# Audio_Spektrum_Analysator.net
KiCad netlist of a schematic drawn in EAGLE
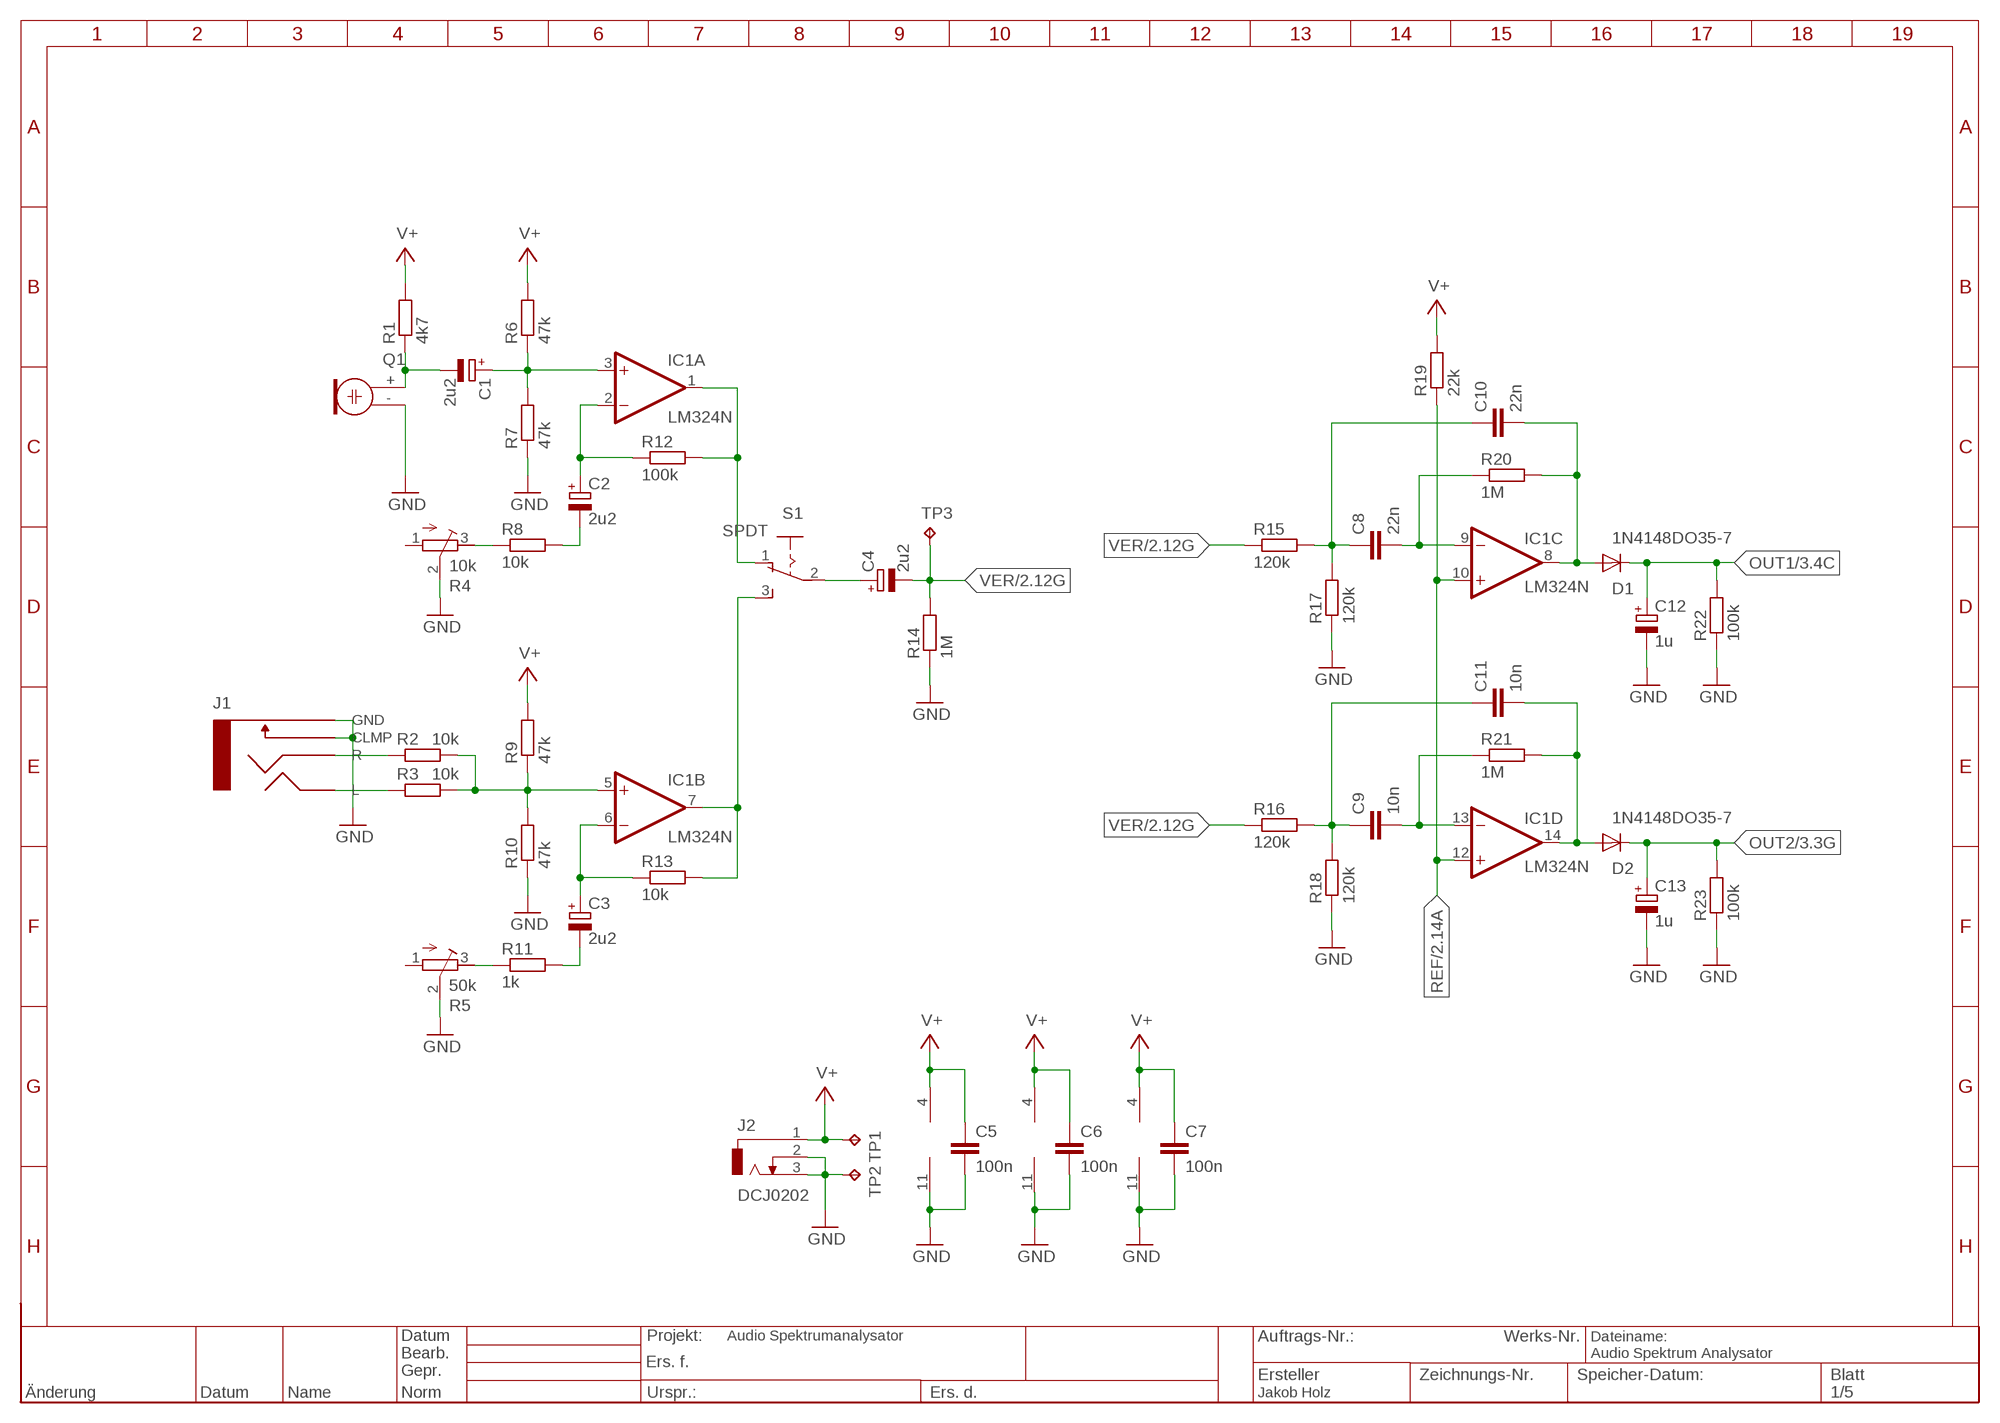
[diagram p0: schematic, sheet 1]
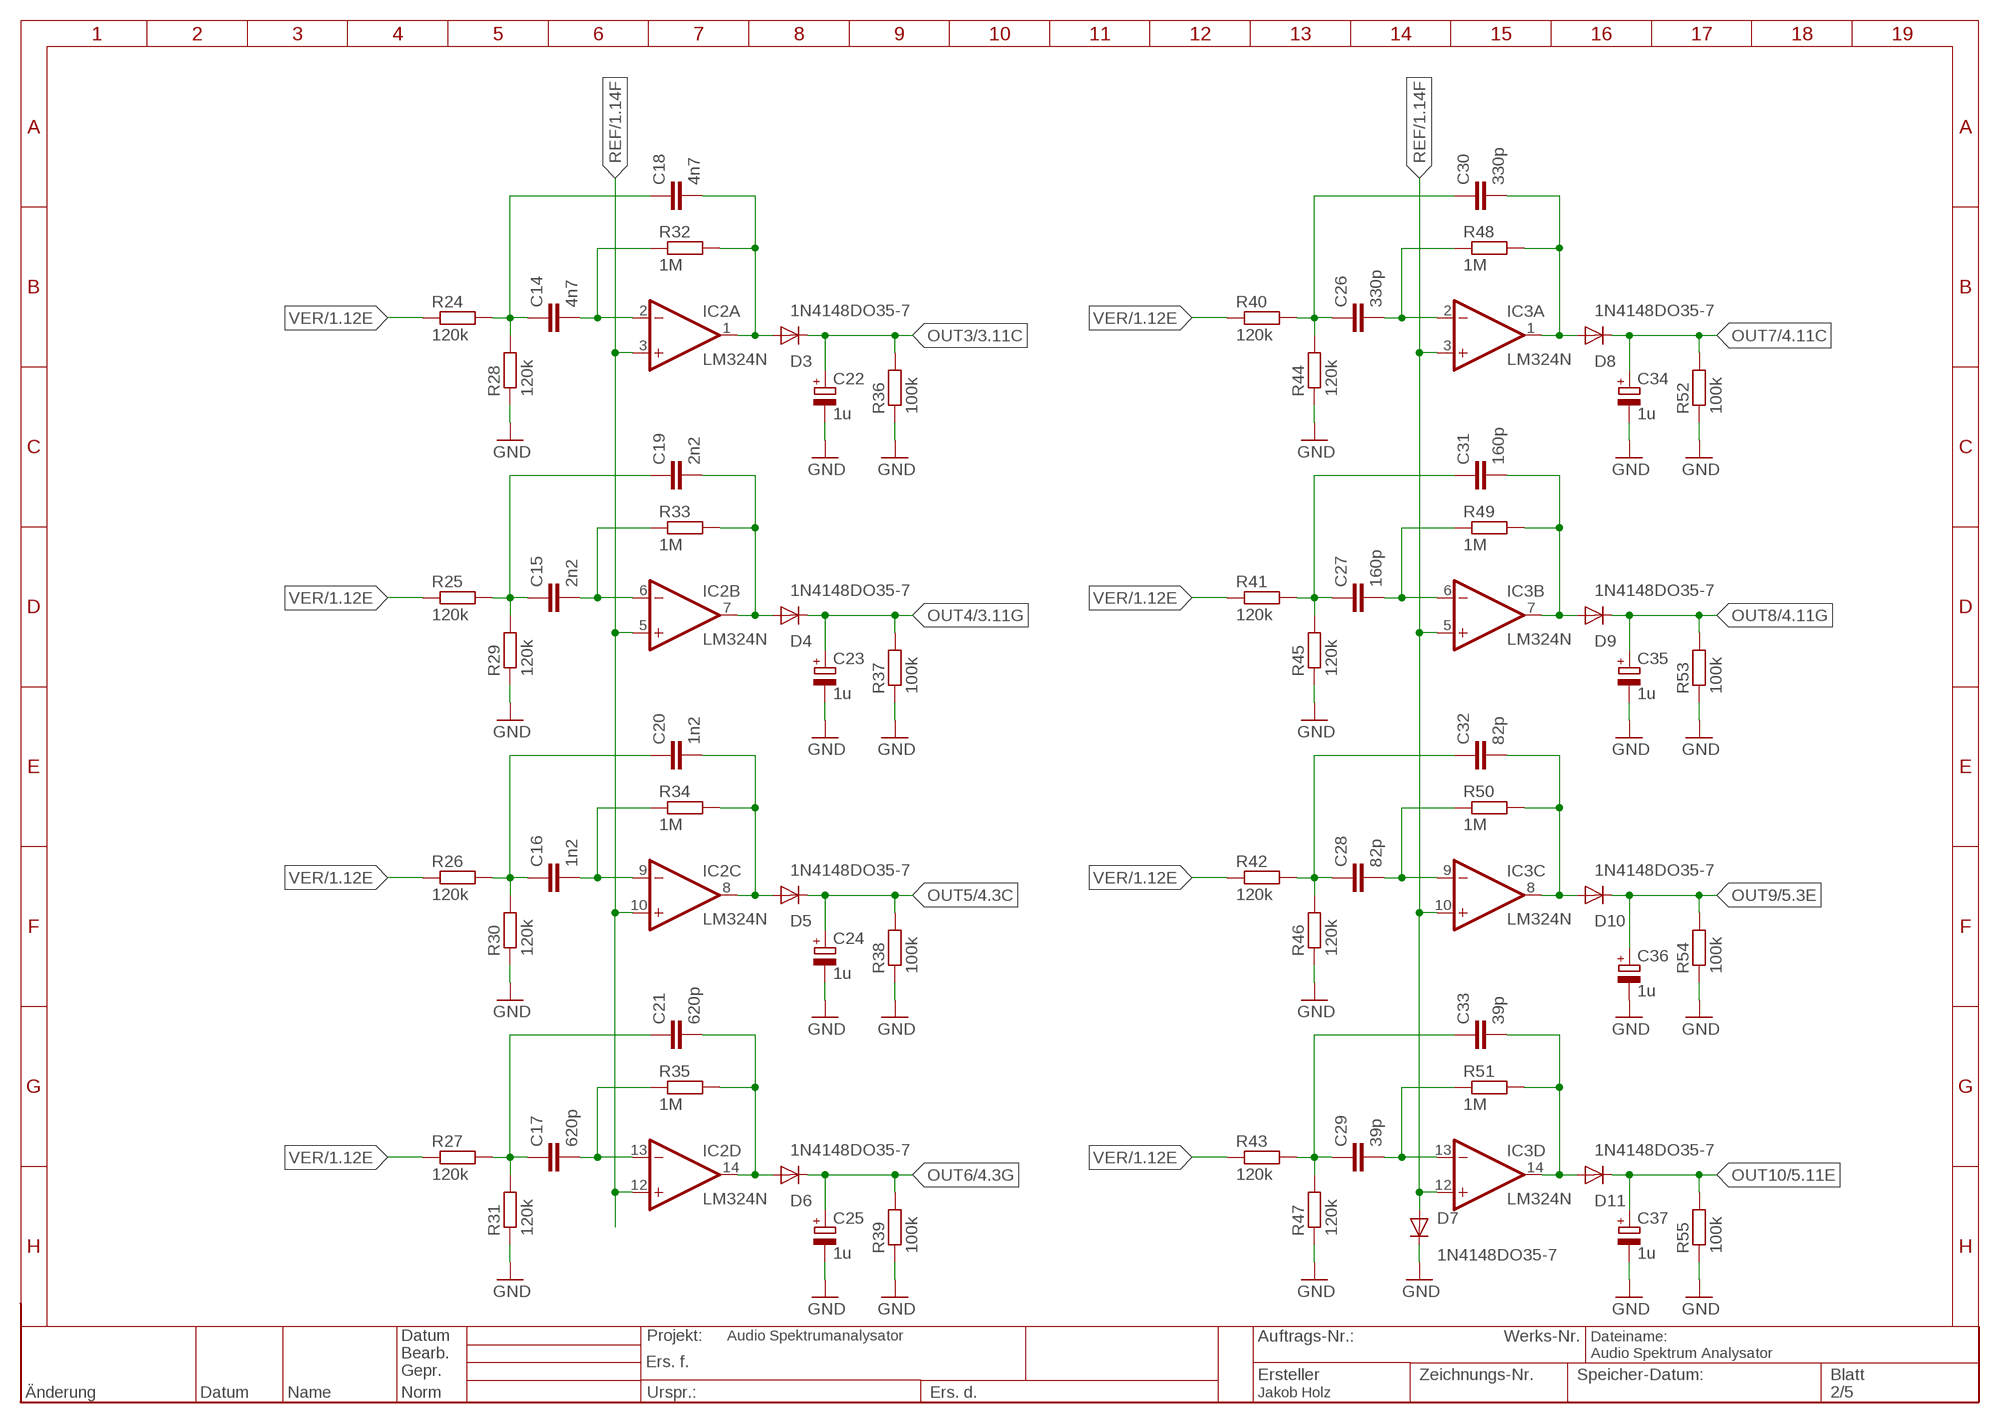
[diagram p1: schematic, sheet 2]
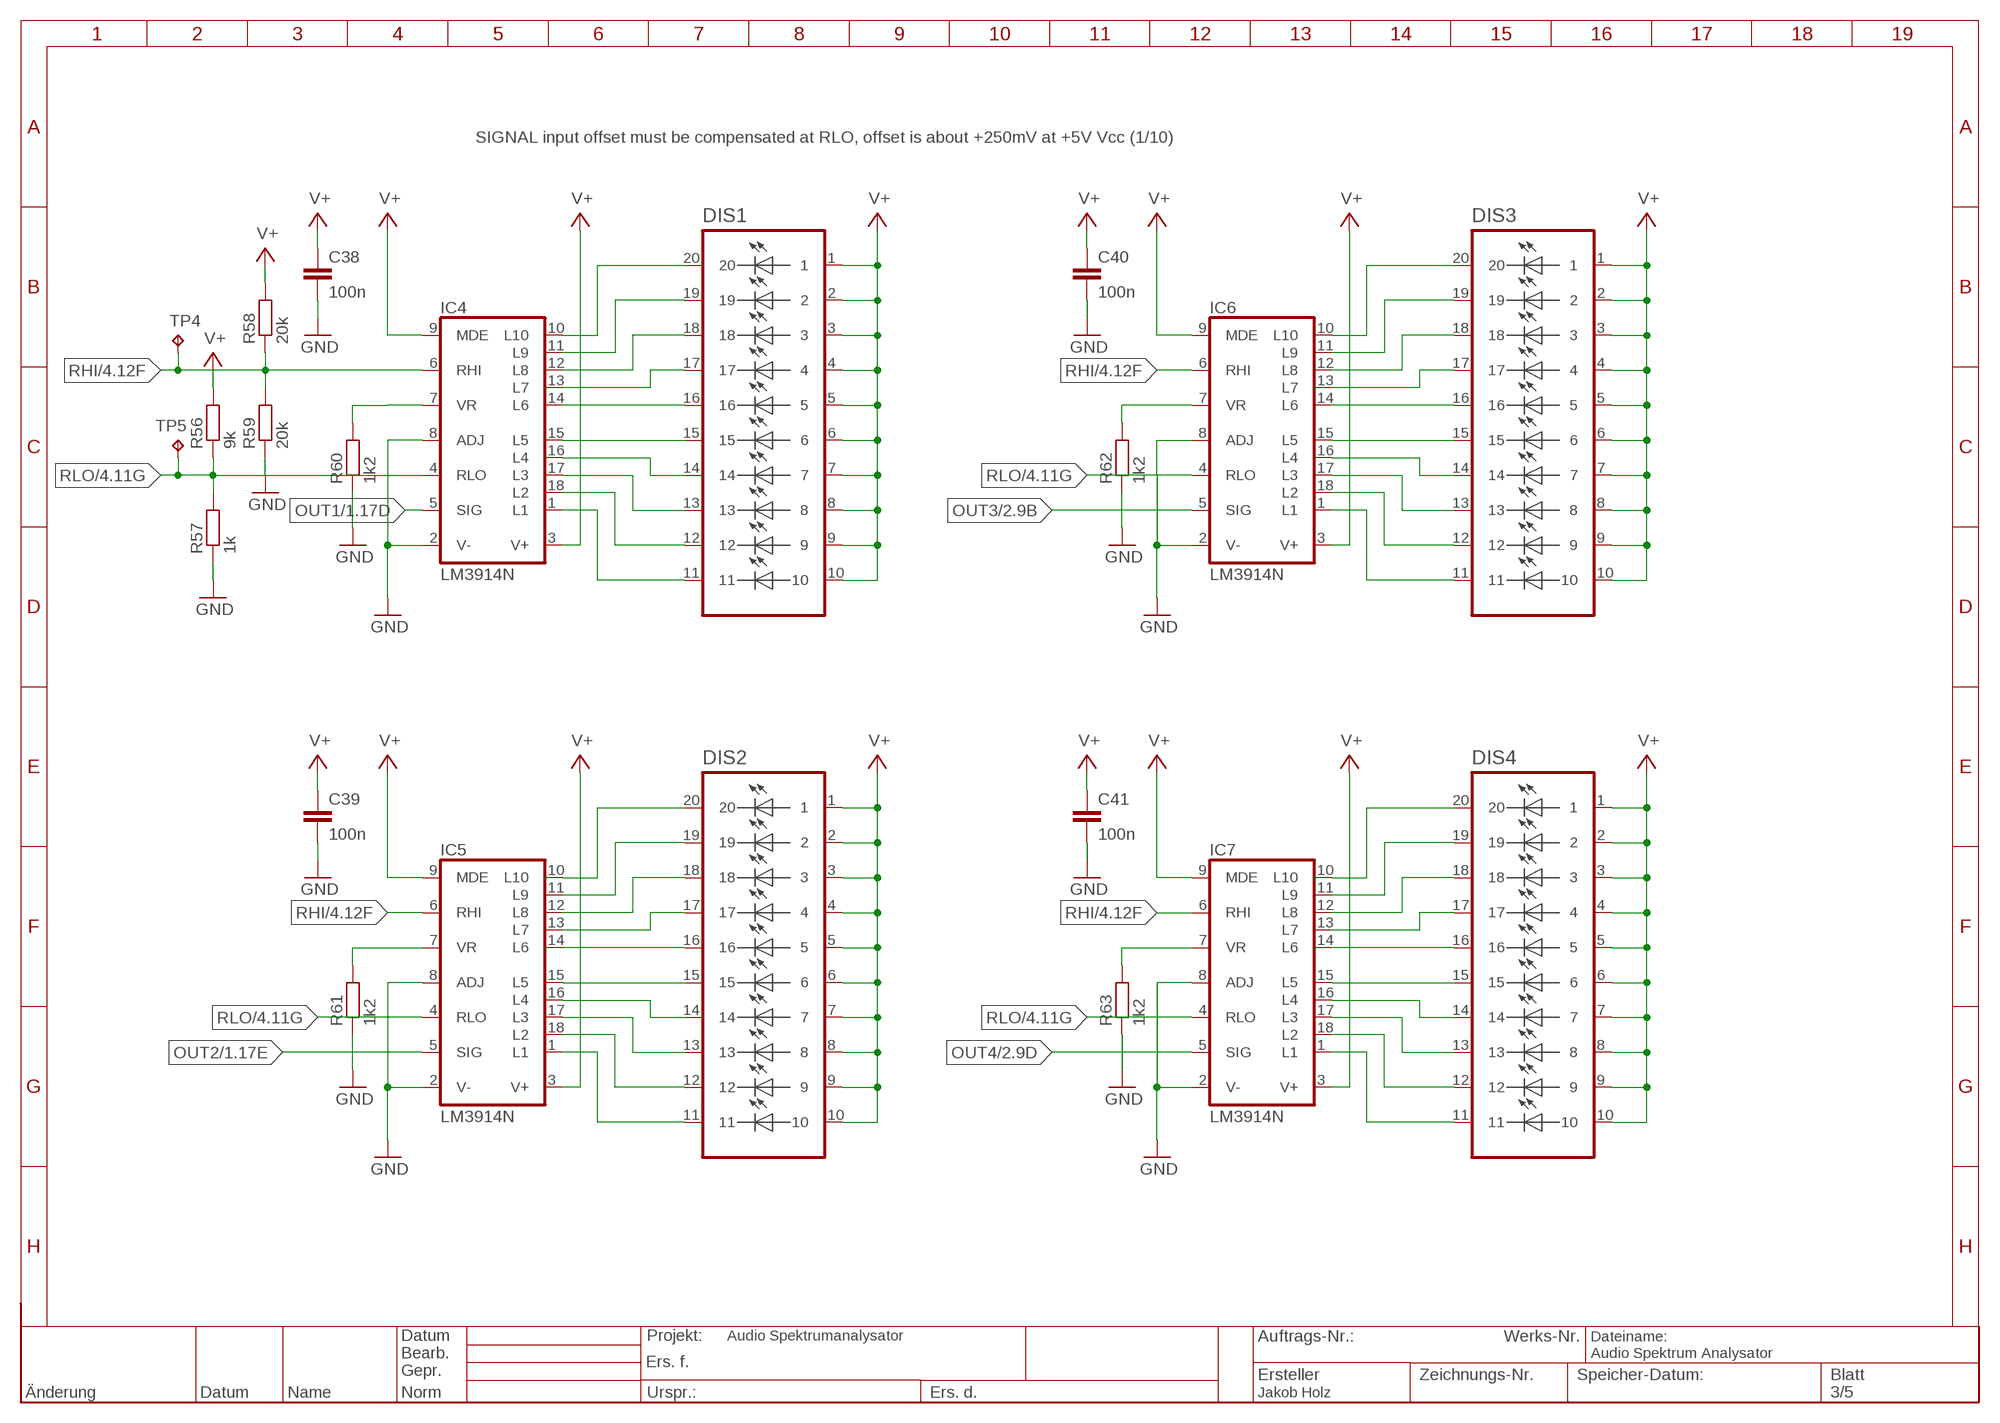
[diagram p2: schematic, sheet 3]
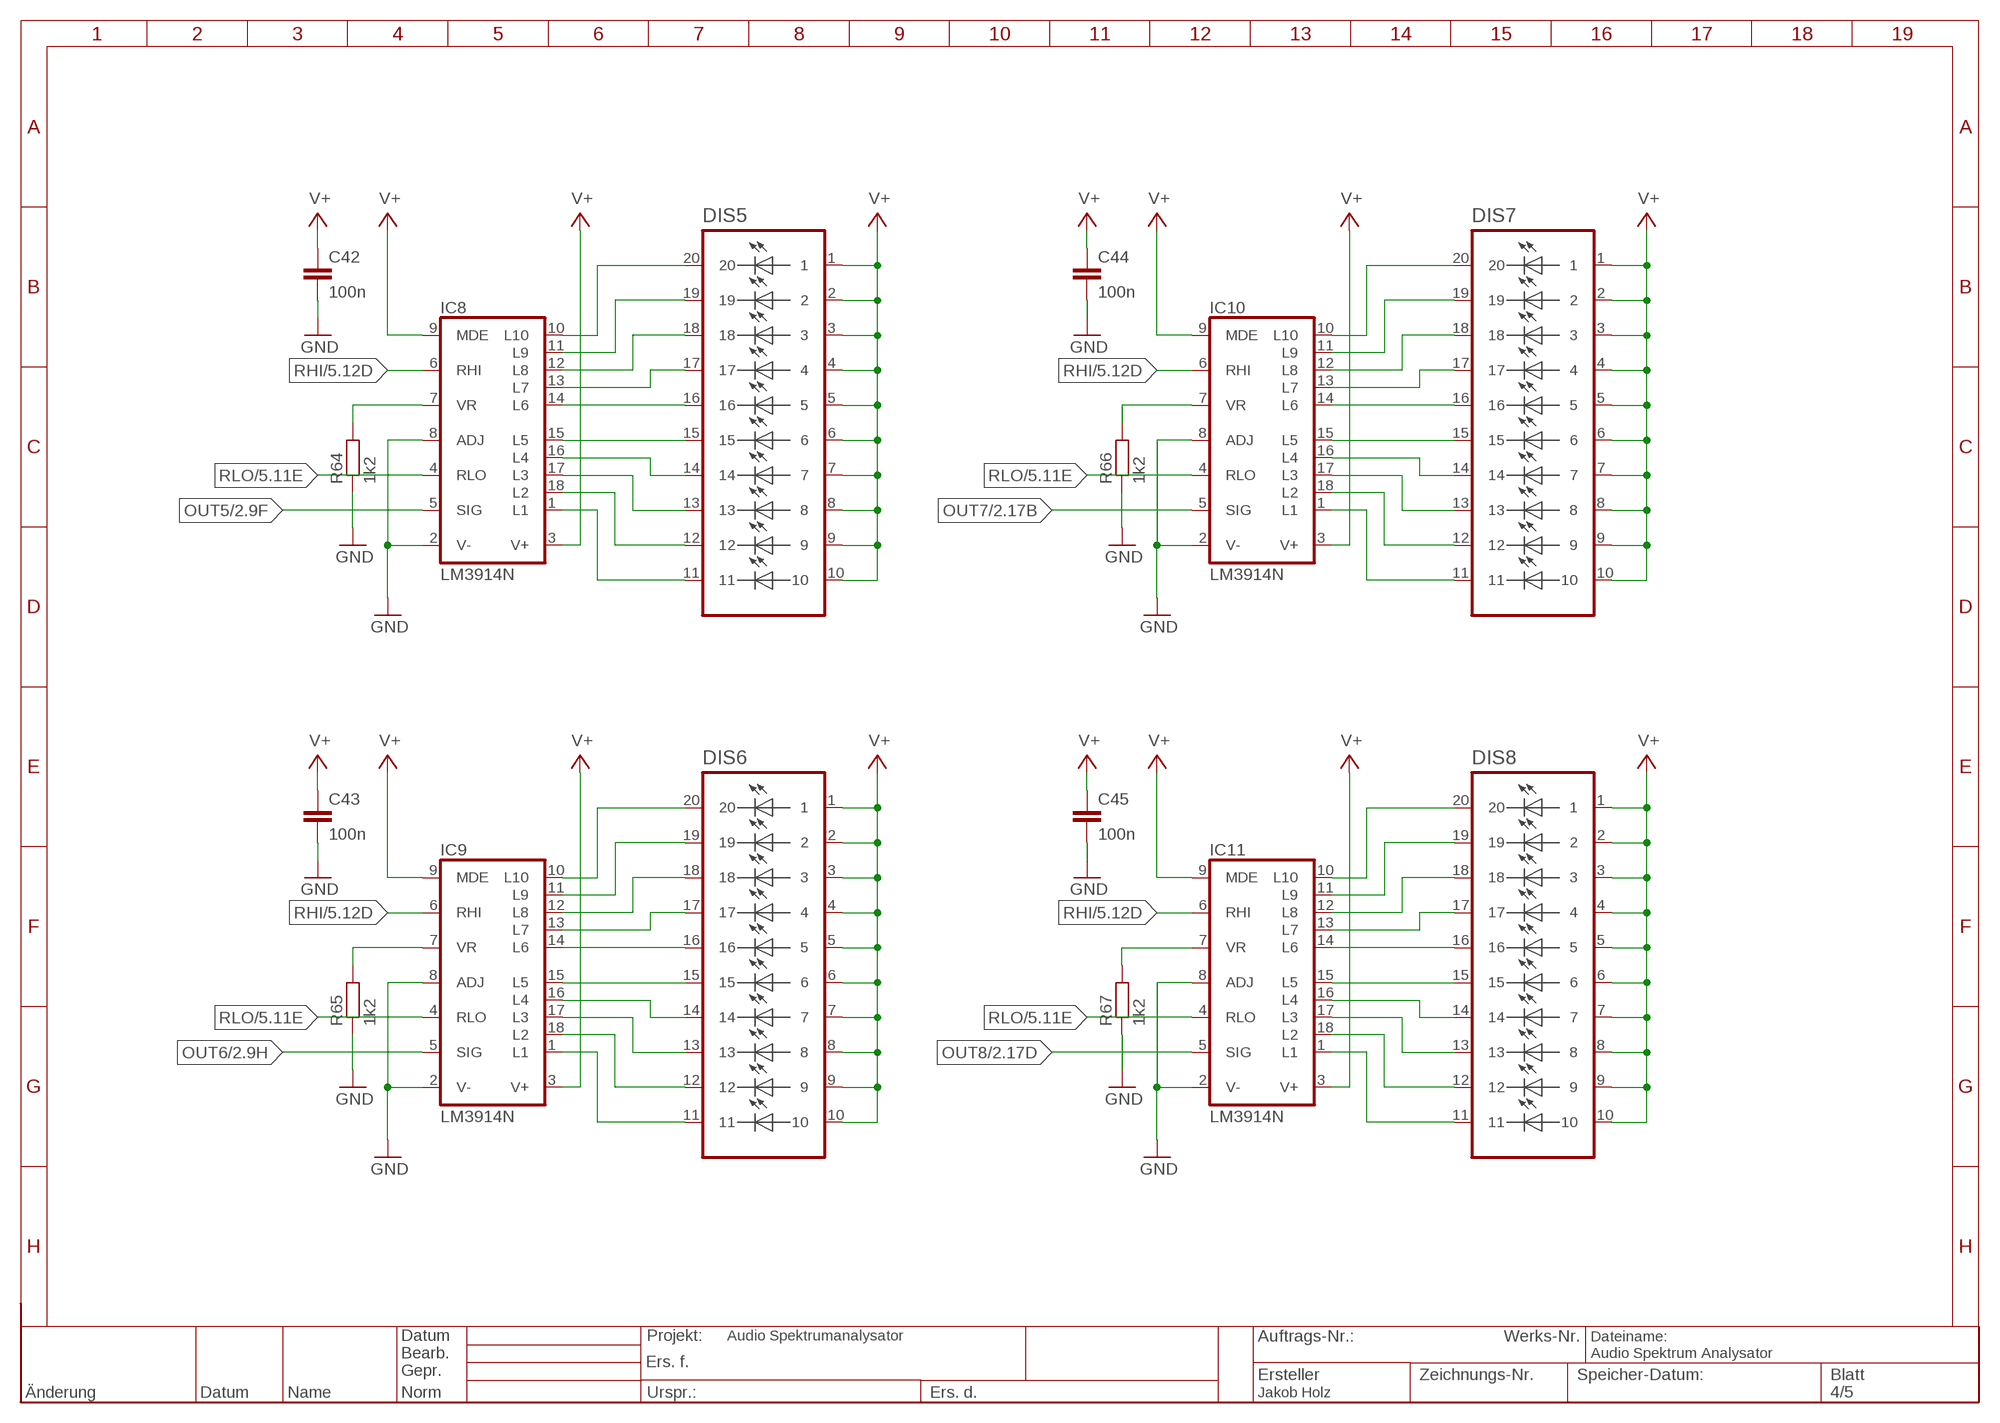
[diagram p3: schematic, sheet 4]
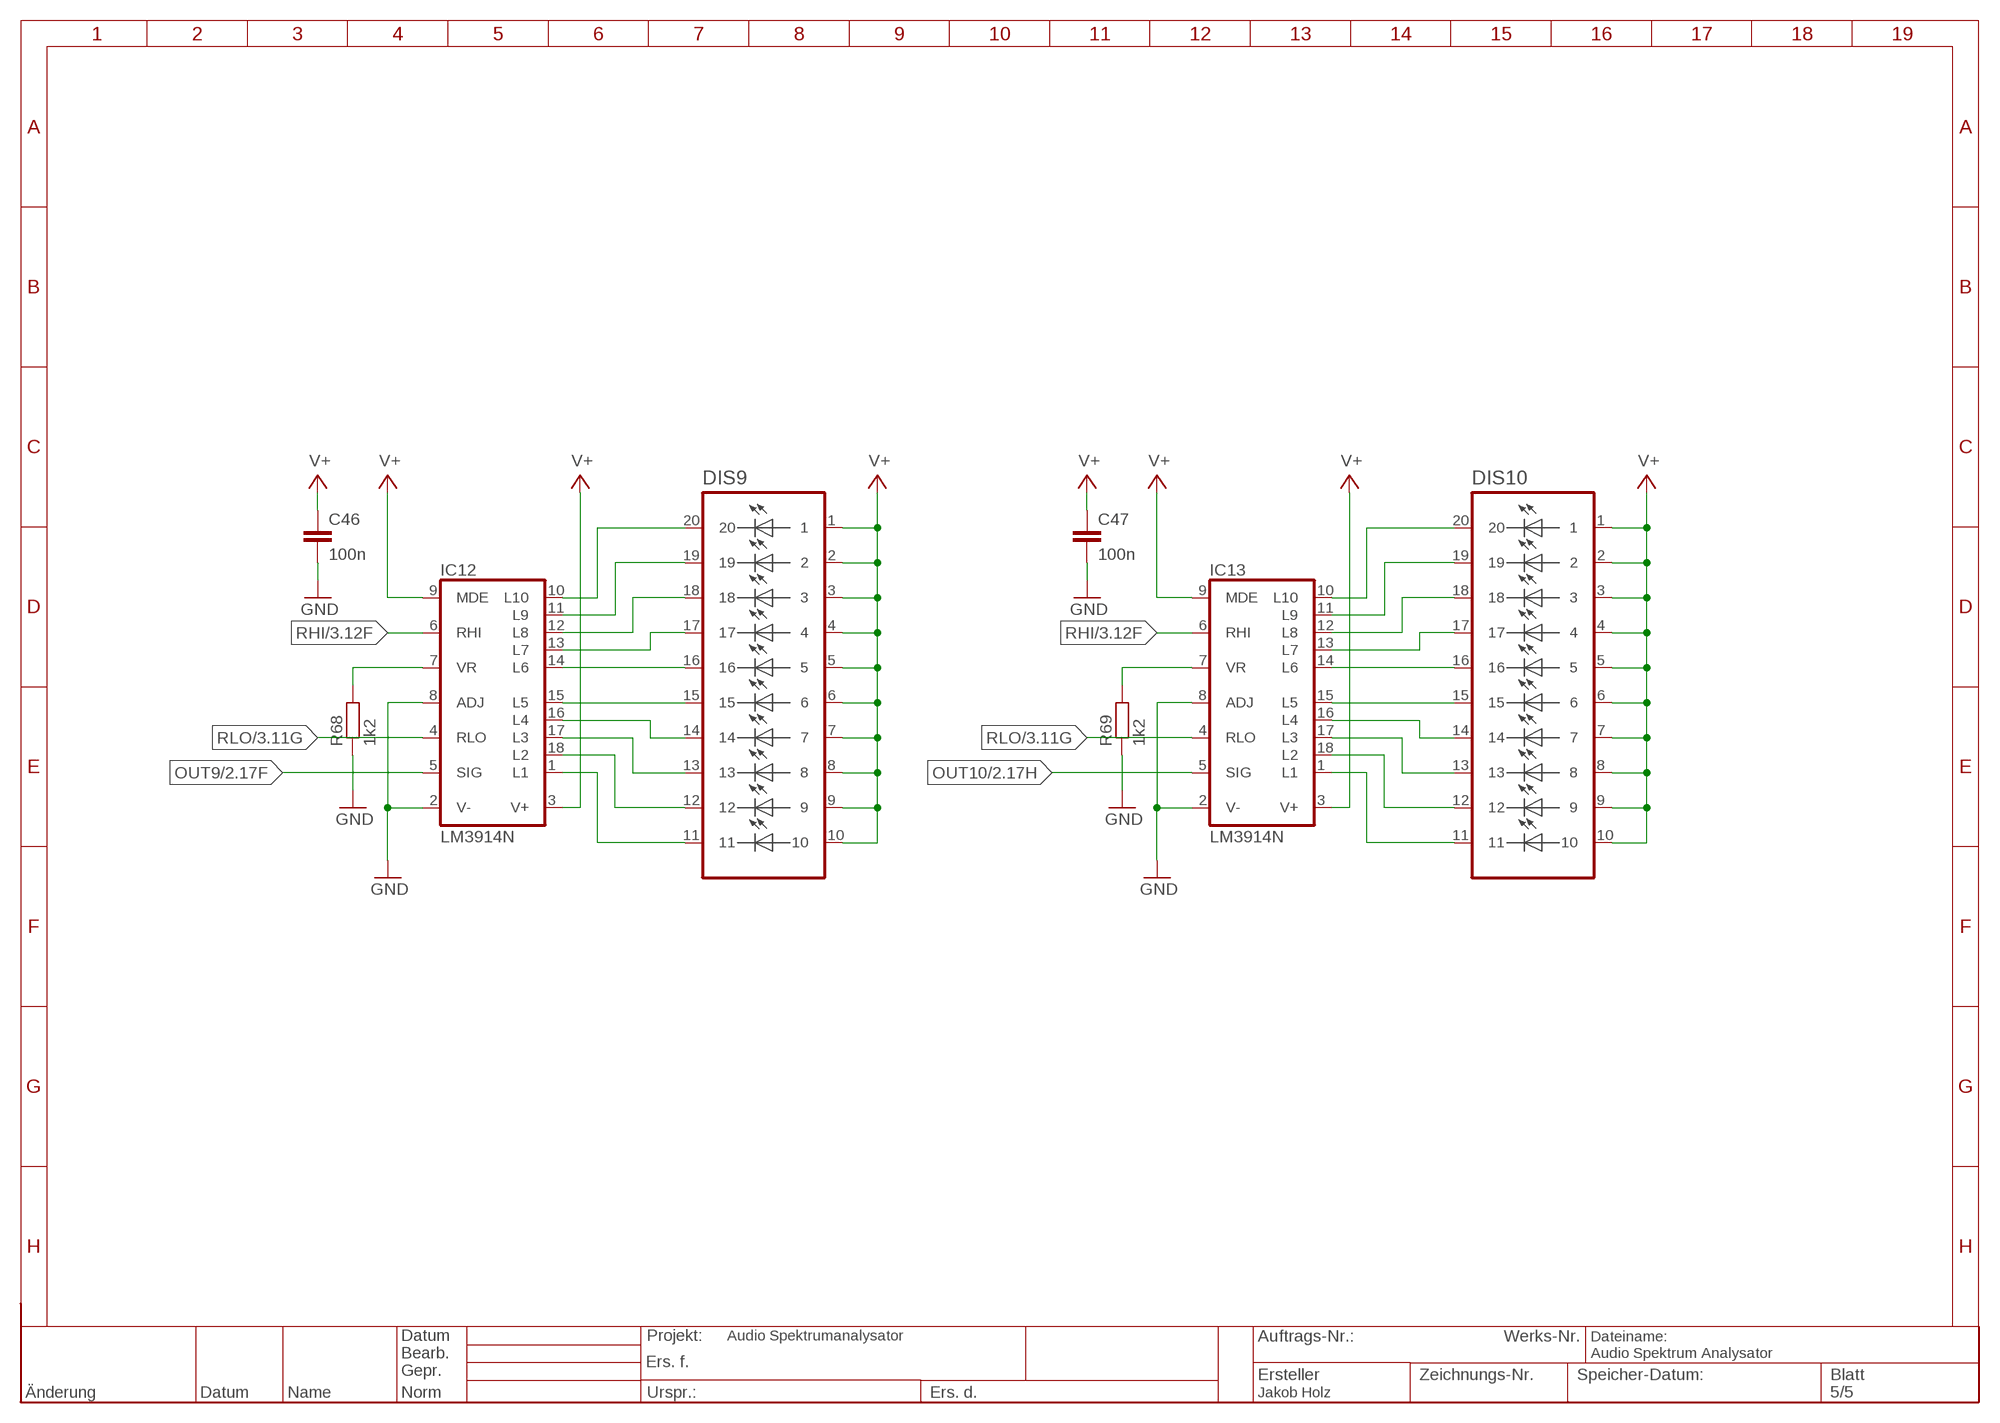
[diagram p4: schematic, sheet 5]

(export (version "E")
  (design (tool "Eeschema 10.0.6"))
  (components
    (comp (ref "C42")
      (value "100n")
      (footprint "eagle-import:C050-024X044")
      (libsource (lib "eagle-import") (part "C-EU050-024X044"))
    )
    (comp (ref "C43")
      (value "100n")
      (footprint "eagle-import:C050-024X044")
      (libsource (lib "eagle-import") (part "C-EU050-024X044"))
    )
    (comp (ref "C44")
      (value "100n")
      (footprint "eagle-import:C050-024X044")
      (libsource (lib "eagle-import") (part "C-EU050-024X044"))
    )
    (comp (ref "C45")
      (value "100n")
      (footprint "eagle-import:C050-024X044")
      (libsource (lib "eagle-import") (part "C-EU050-024X044"))
    )
    (comp (ref "DIS5")
      (value "SHB10R")
      (footprint "eagle-import:SHB10R")
      (libsource (lib "eagle-import") (part "SHB10R"))
    )
    (comp (ref "DIS6")
      (value "SHB10R")
      (footprint "eagle-import:SHB10R")
      (libsource (lib "eagle-import") (part "SHB10R"))
    )
    (comp (ref "DIS7")
      (value "SHB10R")
      (footprint "eagle-import:SHB10R")
      (libsource (lib "eagle-import") (part "SHB10R"))
    )
    (comp (ref "DIS8")
      (value "SHB10R")
      (footprint "eagle-import:SHB10R")
      (libsource (lib "eagle-import") (part "SHB10R"))
    )
    (comp (ref "IC8")
      (value "LM3914N")
      (footprint "eagle-import:DIL18")
      (libsource (lib "eagle-import") (part "LM3914N"))
    )
    (comp (ref "IC9")
      (value "LM3914N")
      (footprint "eagle-import:DIL18")
      (libsource (lib "eagle-import") (part "LM3914N"))
    )
    (comp (ref "IC10")
      (value "LM3914N")
      (footprint "eagle-import:DIL18")
      (libsource (lib "eagle-import") (part "LM3914N"))
    )
    (comp (ref "IC11")
      (value "LM3914N")
      (footprint "eagle-import:DIL18")
      (libsource (lib "eagle-import") (part "LM3914N"))
    )
    (comp (ref "R64")
      (value "1k2")
      (footprint "eagle-import:0207_7")
      (libsource (lib "eagle-import") (part "resistor_348_R-EU_0207/7"))
    )
    (comp (ref "R65")
      (value "1k2")
      (footprint "eagle-import:0207_7")
      (libsource (lib "eagle-import") (part "resistor_348_R-EU_0207/7"))
    )
    (comp (ref "R66")
      (value "1k2")
      (footprint "eagle-import:0207_7")
      (libsource (lib "eagle-import") (part "resistor_348_R-EU_0207/7"))
    )
    (comp (ref "R67")
      (value "1k2")
      (footprint "eagle-import:0207_7")
      (libsource (lib "eagle-import") (part "resistor_348_R-EU_0207/7"))
    )
    (comp (ref "C1")
      (value "2u2")
      (footprint "eagle-import:E2,5-5")
      (libsource (lib "eagle-import") (part "CPOL-EUE2.5-5"))
    )
    (comp (ref "C2")
      (value "2u2")
      (footprint "eagle-import:E2,5-5")
      (libsource (lib "eagle-import") (part "CPOL-EUE2.5-5"))
    )
    (comp (ref "C3")
      (value "2u2")
      (footprint "eagle-import:E2,5-5")
      (libsource (lib "eagle-import") (part "CPOL-EUE2.5-5"))
    )
    (comp (ref "C4")
      (value "2u2")
      (footprint "eagle-import:E2,5-5")
      (libsource (lib "eagle-import") (part "CPOL-EUE2.5-5"))
    )
    (comp (ref "C5")
      (value "100n")
      (footprint "eagle-import:C050-024X044")
      (libsource (lib "eagle-import") (part "C-EU050-024X044"))
    )
    (comp (ref "C6")
      (value "100n")
      (footprint "eagle-import:C050-024X044")
      (libsource (lib "eagle-import") (part "C-EU050-024X044"))
    )
    (comp (ref "C7")
      (value "100n")
      (footprint "eagle-import:C050-024X044")
      (libsource (lib "eagle-import") (part "C-EU050-024X044"))
    )
    (comp (ref "C8")
      (value "22n")
      (footprint "eagle-import:C025-024X044")
      (libsource (lib "eagle-import") (part "C-EU025-024X044"))
    )
    (comp (ref "C9")
      (value "10n")
      (footprint "eagle-import:C025-024X044")
      (libsource (lib "eagle-import") (part "C-EU025-024X044"))
    )
    (comp (ref "C10")
      (value "22n")
      (footprint "eagle-import:C025-024X044")
      (libsource (lib "eagle-import") (part "C-EU025-024X044"))
    )
    (comp (ref "C11")
      (value "10n")
      (footprint "eagle-import:C025-024X044")
      (libsource (lib "eagle-import") (part "C-EU025-024X044"))
    )
    (comp (ref "C12")
      (value "1u")
      (footprint "eagle-import:E2,5-5")
      (libsource (lib "eagle-import") (part "CPOL-EUE2.5-5"))
    )
    (comp (ref "C13")
      (value "1u")
      (footprint "eagle-import:E2,5-5")
      (libsource (lib "eagle-import") (part "CPOL-EUE2.5-5"))
    )
    (comp (ref "D1")
      (value "1N4148DO35-7")
      (footprint "eagle-import:DO35-7")
      (libsource (lib "eagle-import") (part "1N4148DO35-7"))
    )
    (comp (ref "D2")
      (value "1N4148DO35-7")
      (footprint "eagle-import:DO35-7")
      (libsource (lib "eagle-import") (part "1N4148DO35-7"))
    )
    (comp (ref "IC1")
      (value "LM324N")
      (footprint "eagle-import:DIL14")
      (libsource (lib "eagle-import") (part "LM324N"))
    )
    (comp (ref "IC2")
      (value "LM324N")
      (footprint "eagle-import:DIL14")
      (libsource (lib "eagle-import") (part "LM324N"))
    )
    (comp (ref "IC3")
      (value "LM324N")
      (footprint "eagle-import:DIL14")
      (libsource (lib "eagle-import") (part "LM324N"))
    )
    (comp (ref "J1")
      (value "2.5MM-AUXS")
      (footprint "eagle-import:2,5MM-AUX_JACK")
      (libsource (lib "eagle-import") (part "2.5MM-AUXS"))
    )
    (comp (ref "J2")
      (value "DCJ0202")
      (footprint "eagle-import:DCJ0202")
      (libsource (lib "eagle-import") (part "DCJ0202"))
    )
    (comp (ref "Q1")
      (value "ELECTRET")
      (footprint "eagle-import:9.7ELECTRET")
      (libsource (lib "eagle-import") (part "ELECTRET"))
    )
    (comp (ref "R1")
      (value "4k7")
      (footprint "eagle-import:0207_7")
      (libsource (lib "eagle-import") (part "R-EU_0207/7"))
    )
    (comp (ref "R2")
      (value "10k")
      (footprint "eagle-import:0207_7")
      (libsource (lib "eagle-import") (part "R-EU_0207/7"))
    )
    (comp (ref "R3")
      (value "10k")
      (footprint "eagle-import:0207_7")
      (libsource (lib "eagle-import") (part "R-EU_0207/7"))
    )
    (comp (ref "R4")
      (value "10k")
      (footprint "eagle-import:RTRIM64W")
      (libsource (lib "eagle-import") (part "R-TRIMM64W"))
    )
    (comp (ref "R5")
      (value "50k")
      (footprint "eagle-import:RTRIM64W")
      (libsource (lib "eagle-import") (part "R-TRIMM64W"))
    )
    (comp (ref "R6")
      (value "47k")
      (footprint "eagle-import:0207_7")
      (libsource (lib "eagle-import") (part "R-EU_0207/7"))
    )
    (comp (ref "R7")
      (value "47k")
      (footprint "eagle-import:0207_7")
      (libsource (lib "eagle-import") (part "R-EU_0207/7"))
    )
    (comp (ref "R8")
      (value "10k")
      (footprint "eagle-import:0207_7")
      (libsource (lib "eagle-import") (part "R-EU_0207/7"))
    )
    (comp (ref "R9")
      (value "47k")
      (footprint "eagle-import:0207_7")
      (libsource (lib "eagle-import") (part "R-EU_0207/7"))
    )
    (comp (ref "R10")
      (value "47k")
      (footprint "eagle-import:0207_7")
      (libsource (lib "eagle-import") (part "R-EU_0207/7"))
    )
    (comp (ref "R11")
      (value "1k")
      (footprint "eagle-import:0207_7")
      (libsource (lib "eagle-import") (part "R-EU_0207/7"))
    )
    (comp (ref "R12")
      (value "100k")
      (footprint "eagle-import:0207_7")
      (libsource (lib "eagle-import") (part "R-EU_0207/7"))
    )
    (comp (ref "R13")
      (value "10k")
      (footprint "eagle-import:0207_7")
      (libsource (lib "eagle-import") (part "resistor_348_R-EU_0207/7"))
    )
    (comp (ref "R14")
      (value "1M")
      (footprint "eagle-import:0207_7")
      (libsource (lib "eagle-import") (part "R-EU_0207/7"))
    )
    (comp (ref "R15")
      (value "120k")
      (footprint "eagle-import:0207_7")
      (libsource (lib "eagle-import") (part "resistor_348_R-EU_0207/7"))
    )
    (comp (ref "R16")
      (value "120k")
      (footprint "eagle-import:0207_7")
      (libsource (lib "eagle-import") (part "resistor_348_R-EU_0207/7"))
    )
    (comp (ref "R17")
      (value "120k")
      (footprint "eagle-import:0207_7")
      (libsource (lib "eagle-import") (part "resistor_348_R-EU_0207/7"))
    )
    (comp (ref "R18")
      (value "120k")
      (footprint "eagle-import:0207_7")
      (libsource (lib "eagle-import") (part "resistor_348_R-EU_0207/7"))
    )
    (comp (ref "R19")
      (value "22k")
      (footprint "eagle-import:0207_7")
      (libsource (lib "eagle-import") (part "resistor_348_R-EU_0207/7"))
    )
    (comp (ref "R20")
      (value "1M")
      (footprint "eagle-import:0207_7")
      (libsource (lib "eagle-import") (part "resistor_348_R-EU_0207/7"))
    )
    (comp (ref "R21")
      (value "1M")
      (footprint "eagle-import:0207_7")
      (libsource (lib "eagle-import") (part "resistor_348_R-EU_0207/7"))
    )
    (comp (ref "R22")
      (value "100k")
      (footprint "eagle-import:0207_7")
      (libsource (lib "eagle-import") (part "R-EU_0207/7"))
    )
    (comp (ref "R23")
      (value "100k")
      (footprint "eagle-import:0207_7")
      (libsource (lib "eagle-import") (part "R-EU_0207/7"))
    )
    (comp (ref "S1")
      (value "SPDT")
      (footprint "eagle-import:SPDT")
      (libsource (lib "eagle-import") (part "SPDT"))
    )
    (comp (ref "TP1")
      (value "TPPAD1-20")
      (footprint "eagle-import:P1-20")
      (libsource (lib "eagle-import") (part "TPPAD1-20"))
    )
    (comp (ref "TP2")
      (value "TPPAD1-20")
      (footprint "eagle-import:P1-20")
      (libsource (lib "eagle-import") (part "TPPAD1-20"))
    )
    (comp (ref "TP3")
      (value "TPPAD1-20")
      (footprint "eagle-import:P1-20")
      (libsource (lib "eagle-import") (part "TPPAD1-20"))
    )
    (comp (ref "C14")
      (value "4n7")
      (footprint "eagle-import:C025-024X044")
      (libsource (lib "eagle-import") (part "C-EU025-024X044"))
    )
    (comp (ref "C15")
      (value "2n2")
      (footprint "eagle-import:C025-024X044")
      (libsource (lib "eagle-import") (part "C-EU025-024X044"))
    )
    (comp (ref "C16")
      (value "1n2")
      (footprint "eagle-import:C025-024X044")
      (libsource (lib "eagle-import") (part "C-EU025-024X044"))
    )
    (comp (ref "C17")
      (value "620p")
      (footprint "eagle-import:C025-024X044")
      (libsource (lib "eagle-import") (part "C-EU025-024X044"))
    )
    (comp (ref "C18")
      (value "4n7")
      (footprint "eagle-import:C025-024X044")
      (libsource (lib "eagle-import") (part "C-EU025-024X044"))
    )
    (comp (ref "C19")
      (value "2n2")
      (footprint "eagle-import:C025-024X044")
      (libsource (lib "eagle-import") (part "C-EU025-024X044"))
    )
    (comp (ref "C20")
      (value "1n2")
      (footprint "eagle-import:C025-024X044")
      (libsource (lib "eagle-import") (part "C-EU025-024X044"))
    )
    (comp (ref "C21")
      (value "620p")
      (footprint "eagle-import:C025-024X044")
      (libsource (lib "eagle-import") (part "C-EU025-024X044"))
    )
    (comp (ref "C22")
      (value "1u")
      (footprint "eagle-import:E2,5-5")
      (libsource (lib "eagle-import") (part "CPOL-EUE2.5-5"))
    )
    (comp (ref "C23")
      (value "1u")
      (footprint "eagle-import:E2,5-5")
      (libsource (lib "eagle-import") (part "CPOL-EUE2.5-5"))
    )
    (comp (ref "C24")
      (value "1u")
      (footprint "eagle-import:E2,5-5")
      (libsource (lib "eagle-import") (part "CPOL-EUE2.5-5"))
    )
    (comp (ref "C25")
      (value "1u")
      (footprint "eagle-import:E2,5-5")
      (libsource (lib "eagle-import") (part "CPOL-EUE2.5-5"))
    )
    (comp (ref "C26")
      (value "330p")
      (footprint "eagle-import:C025-024X044")
      (libsource (lib "eagle-import") (part "C-EU025-024X044"))
    )
    (comp (ref "C27")
      (value "160p")
      (footprint "eagle-import:C025-024X044")
      (libsource (lib "eagle-import") (part "C-EU025-024X044"))
    )
    (comp (ref "C28")
      (value "82p")
      (footprint "eagle-import:C025-024X044")
      (libsource (lib "eagle-import") (part "C-EU025-024X044"))
    )
    (comp (ref "C29")
      (value "39p")
      (footprint "eagle-import:C025-024X044")
      (libsource (lib "eagle-import") (part "C-EU025-024X044"))
    )
    (comp (ref "C30")
      (value "330p")
      (footprint "eagle-import:C025-024X044")
      (libsource (lib "eagle-import") (part "C-EU025-024X044"))
    )
    (comp (ref "C31")
      (value "160p")
      (footprint "eagle-import:C025-024X044")
      (libsource (lib "eagle-import") (part "C-EU025-024X044"))
    )
    (comp (ref "C32")
      (value "82p")
      (footprint "eagle-import:C025-024X044")
      (libsource (lib "eagle-import") (part "C-EU025-024X044"))
    )
    (comp (ref "C33")
      (value "39p")
      (footprint "eagle-import:C025-024X044")
      (libsource (lib "eagle-import") (part "C-EU025-024X044"))
    )
    (comp (ref "C34")
      (value "1u")
      (footprint "eagle-import:E2,5-5")
      (libsource (lib "eagle-import") (part "CPOL-EUE2.5-5"))
    )
    (comp (ref "C35")
      (value "1u")
      (footprint "eagle-import:E2,5-5")
      (libsource (lib "eagle-import") (part "CPOL-EUE2.5-5"))
    )
    (comp (ref "C36")
      (value "1u")
      (footprint "eagle-import:E2,5-5")
      (libsource (lib "eagle-import") (part "CPOL-EUE2.5-5"))
    )
    (comp (ref "C37")
      (value "1u")
      (footprint "eagle-import:E2,5-5")
      (libsource (lib "eagle-import") (part "CPOL-EUE2.5-5"))
    )
    (comp (ref "D3")
      (value "1N4148DO35-7")
      (footprint "eagle-import:DO35-7")
      (libsource (lib "eagle-import") (part "1N4148DO35-7"))
    )
    (comp (ref "D4")
      (value "1N4148DO35-7")
      (footprint "eagle-import:DO35-7")
      (libsource (lib "eagle-import") (part "1N4148DO35-7"))
    )
    (comp (ref "D5")
      (value "1N4148DO35-7")
      (footprint "eagle-import:DO35-7")
      (libsource (lib "eagle-import") (part "1N4148DO35-7"))
    )
    (comp (ref "D6")
      (value "1N4148DO35-7")
      (footprint "eagle-import:DO35-7")
      (libsource (lib "eagle-import") (part "1N4148DO35-7"))
    )
    (comp (ref "D7")
      (value "1N4148DO35-7")
      (footprint "eagle-import:DO35-7")
      (libsource (lib "eagle-import") (part "1N4148DO35-7"))
    )
    (comp (ref "D8")
      (value "1N4148DO35-7")
      (footprint "eagle-import:DO35-7")
      (libsource (lib "eagle-import") (part "1N4148DO35-7"))
    )
    (comp (ref "D9")
      (value "1N4148DO35-7")
      (footprint "eagle-import:DO35-7")
      (libsource (lib "eagle-import") (part "1N4148DO35-7"))
    )
    (comp (ref "D10")
      (value "1N4148DO35-7")
      (footprint "eagle-import:DO35-7")
      (libsource (lib "eagle-import") (part "1N4148DO35-7"))
    )
    (comp (ref "D11")
      (value "1N4148DO35-7")
      (footprint "eagle-import:DO35-7")
      (libsource (lib "eagle-import") (part "1N4148DO35-7"))
    )
    (comp (ref "R24")
      (value "120k")
      (footprint "eagle-import:0207_7")
      (libsource (lib "eagle-import") (part "resistor_348_R-EU_0207/7"))
    )
    (comp (ref "R25")
      (value "120k")
      (footprint "eagle-import:0207_7")
      (libsource (lib "eagle-import") (part "resistor_348_R-EU_0207/7"))
    )
    (comp (ref "R26")
      (value "120k")
      (footprint "eagle-import:0207_7")
      (libsource (lib "eagle-import") (part "resistor_348_R-EU_0207/7"))
    )
    (comp (ref "R27")
      (value "120k")
      (footprint "eagle-import:0207_7")
      (libsource (lib "eagle-import") (part "resistor_348_R-EU_0207/7"))
    )
    (comp (ref "R28")
      (value "120k")
      (footprint "eagle-import:0207_7")
      (libsource (lib "eagle-import") (part "resistor_348_R-EU_0207/7"))
    )
    (comp (ref "R29")
      (value "120k")
      (footprint "eagle-import:0207_7")
      (libsource (lib "eagle-import") (part "resistor_348_R-EU_0207/7"))
    )
    (comp (ref "R30")
      (value "120k")
      (footprint "eagle-import:0207_7")
      (libsource (lib "eagle-import") (part "resistor_348_R-EU_0207/7"))
    )
    (comp (ref "R31")
      (value "120k")
      (footprint "eagle-import:0207_7")
      (libsource (lib "eagle-import") (part "resistor_348_R-EU_0207/7"))
    )
    (comp (ref "R32")
      (value "1M")
      (footprint "eagle-import:0207_7")
      (libsource (lib "eagle-import") (part "resistor_348_R-EU_0207/7"))
    )
    (comp (ref "R33")
      (value "1M")
      (footprint "eagle-import:0207_7")
      (libsource (lib "eagle-import") (part "resistor_348_R-EU_0207/7"))
    )
    (comp (ref "R34")
      (value "1M")
      (footprint "eagle-import:0207_7")
      (libsource (lib "eagle-import") (part "resistor_348_R-EU_0207/7"))
    )
    (comp (ref "R35")
      (value "1M")
      (footprint "eagle-import:0207_7")
      (libsource (lib "eagle-import") (part "resistor_348_R-EU_0207/7"))
    )
    (comp (ref "R36")
      (value "100k")
      (footprint "eagle-import:0207_7")
      (libsource (lib "eagle-import") (part "R-EU_0207/7"))
    )
    (comp (ref "R37")
      (value "100k")
      (footprint "eagle-import:0207_7")
      (libsource (lib "eagle-import") (part "R-EU_0207/7"))
    )
    (comp (ref "R38")
      (value "100k")
      (footprint "eagle-import:0207_7")
      (libsource (lib "eagle-import") (part "R-EU_0207/7"))
    )
    (comp (ref "R39")
      (value "100k")
      (footprint "eagle-import:0207_7")
      (libsource (lib "eagle-import") (part "R-EU_0207/7"))
    )
    (comp (ref "R40")
      (value "120k")
      (footprint "eagle-import:0207_7")
      (libsource (lib "eagle-import") (part "resistor_348_R-EU_0207/7"))
    )
    (comp (ref "R41")
      (value "120k")
      (footprint "eagle-import:0207_7")
      (libsource (lib "eagle-import") (part "resistor_348_R-EU_0207/7"))
    )
    (comp (ref "R42")
      (value "120k")
      (footprint "eagle-import:0207_7")
      (libsource (lib "eagle-import") (part "resistor_348_R-EU_0207/7"))
    )
    (comp (ref "R43")
      (value "120k")
      (footprint "eagle-import:0207_7")
      (libsource (lib "eagle-import") (part "resistor_348_R-EU_0207/7"))
    )
    (comp (ref "R44")
      (value "120k")
      (footprint "eagle-import:0207_7")
      (libsource (lib "eagle-import") (part "resistor_348_R-EU_0207/7"))
    )
    (comp (ref "R45")
      (value "120k")
      (footprint "eagle-import:0207_7")
      (libsource (lib "eagle-import") (part "resistor_348_R-EU_0207/7"))
    )
    (comp (ref "R46")
      (value "120k")
      (footprint "eagle-import:0207_7")
      (libsource (lib "eagle-import") (part "resistor_348_R-EU_0207/7"))
    )
    (comp (ref "R47")
      (value "120k")
      (footprint "eagle-import:0207_7")
      (libsource (lib "eagle-import") (part "resistor_348_R-EU_0207/7"))
    )
    (comp (ref "R48")
      (value "1M")
      (footprint "eagle-import:0207_7")
      (libsource (lib "eagle-import") (part "resistor_348_R-EU_0207/7"))
    )
    (comp (ref "R49")
      (value "1M")
      (footprint "eagle-import:0207_7")
      (libsource (lib "eagle-import") (part "resistor_348_R-EU_0207/7"))
    )
    (comp (ref "R50")
      (value "1M")
      (footprint "eagle-import:0207_7")
      (libsource (lib "eagle-import") (part "resistor_348_R-EU_0207/7"))
    )
    (comp (ref "R51")
      (value "1M")
      (footprint "eagle-import:0207_7")
      (libsource (lib "eagle-import") (part "resistor_348_R-EU_0207/7"))
    )
    (comp (ref "R52")
      (value "100k")
      (footprint "eagle-import:0207_7")
      (libsource (lib "eagle-import") (part "R-EU_0207/7"))
    )
    (comp (ref "R53")
      (value "100k")
      (footprint "eagle-import:0207_7")
      (libsource (lib "eagle-import") (part "R-EU_0207/7"))
    )
    (comp (ref "R54")
      (value "100k")
      (footprint "eagle-import:0207_7")
      (libsource (lib "eagle-import") (part "R-EU_0207/7"))
    )
    (comp (ref "R55")
      (value "100k")
      (footprint "eagle-import:0207_7")
      (libsource (lib "eagle-import") (part "R-EU_0207/7"))
    )
    (comp (ref "C38")
      (value "100n")
      (footprint "eagle-import:C050-024X044")
      (libsource (lib "eagle-import") (part "C-EU050-024X044"))
    )
    (comp (ref "C39")
      (value "100n")
      (footprint "eagle-import:C050-024X044")
      (libsource (lib "eagle-import") (part "C-EU050-024X044"))
    )
    (comp (ref "C40")
      (value "100n")
      (footprint "eagle-import:C050-024X044")
      (libsource (lib "eagle-import") (part "C-EU050-024X044"))
    )
    (comp (ref "C41")
      (value "100n")
      (footprint "eagle-import:C050-024X044")
      (libsource (lib "eagle-import") (part "C-EU050-024X044"))
    )
    (comp (ref "DIS1")
      (value "SHB10R")
      (footprint "eagle-import:SHB10R")
      (libsource (lib "eagle-import") (part "SHB10R"))
    )
    (comp (ref "DIS2")
      (value "SHB10R")
      (footprint "eagle-import:SHB10R")
      (libsource (lib "eagle-import") (part "SHB10R"))
    )
    (comp (ref "DIS3")
      (value "SHB10R")
      (footprint "eagle-import:SHB10R")
      (libsource (lib "eagle-import") (part "SHB10R"))
    )
    (comp (ref "DIS4")
      (value "SHB10R")
      (footprint "eagle-import:SHB10R")
      (libsource (lib "eagle-import") (part "SHB10R"))
    )
    (comp (ref "IC4")
      (value "LM3914N")
      (footprint "eagle-import:DIL18")
      (libsource (lib "eagle-import") (part "LM3914N"))
    )
    (comp (ref "IC5")
      (value "LM3914N")
      (footprint "eagle-import:DIL18")
      (libsource (lib "eagle-import") (part "LM3914N"))
    )
    (comp (ref "IC6")
      (value "LM3914N")
      (footprint "eagle-import:DIL18")
      (libsource (lib "eagle-import") (part "LM3914N"))
    )
    (comp (ref "IC7")
      (value "LM3914N")
      (footprint "eagle-import:DIL18")
      (libsource (lib "eagle-import") (part "LM3914N"))
    )
    (comp (ref "R56")
      (value "9k")
      (footprint "eagle-import:0207_7")
      (libsource (lib "eagle-import") (part "resistor_348_R-EU_0207/7"))
    )
    (comp (ref "R57")
      (value "1k")
      (footprint "eagle-import:0207_7")
      (libsource (lib "eagle-import") (part "resistor_348_R-EU_0207/7"))
    )
    (comp (ref "R58")
      (value "20k")
      (footprint "eagle-import:0207_7")
      (libsource (lib "eagle-import") (part "resistor_348_R-EU_0207/7"))
    )
    (comp (ref "R59")
      (value "20k")
      (footprint "eagle-import:0207_7")
      (libsource (lib "eagle-import") (part "resistor_348_R-EU_0207/7"))
    )
    (comp (ref "R60")
      (value "1k2")
      (footprint "eagle-import:0207_7")
      (libsource (lib "eagle-import") (part "resistor_348_R-EU_0207/7"))
    )
    (comp (ref "R61")
      (value "1k2")
      (footprint "eagle-import:0207_7")
      (libsource (lib "eagle-import") (part "resistor_348_R-EU_0207/7"))
    )
    (comp (ref "R62")
      (value "1k2")
      (footprint "eagle-import:0207_7")
      (libsource (lib "eagle-import") (part "resistor_348_R-EU_0207/7"))
    )
    (comp (ref "R63")
      (value "1k2")
      (footprint "eagle-import:0207_7")
      (libsource (lib "eagle-import") (part "resistor_348_R-EU_0207/7"))
    )
    (comp (ref "TP4")
      (value "TPPAD1-20")
      (footprint "eagle-import:P1-20")
      (libsource (lib "eagle-import") (part "TPPAD1-20"))
    )
    (comp (ref "TP5")
      (value "TPPAD1-20")
      (footprint "eagle-import:P1-20")
      (libsource (lib "eagle-import") (part "TPPAD1-20"))
    )
    (comp (ref "C46")
      (value "100n")
      (footprint "eagle-import:C050-024X044")
      (libsource (lib "eagle-import") (part "C-EU050-024X044"))
    )
    (comp (ref "C47")
      (value "100n")
      (footprint "eagle-import:C050-024X044")
      (libsource (lib "eagle-import") (part "C-EU050-024X044"))
    )
    (comp (ref "DIS9")
      (value "SHB10R")
      (footprint "eagle-import:SHB10R")
      (libsource (lib "eagle-import") (part "SHB10R"))
    )
    (comp (ref "DIS10")
      (value "SHB10R")
      (footprint "eagle-import:SHB10R")
      (libsource (lib "eagle-import") (part "SHB10R"))
    )
    (comp (ref "IC12")
      (value "LM3914N")
      (footprint "eagle-import:DIL18")
      (libsource (lib "eagle-import") (part "LM3914N"))
    )
    (comp (ref "IC13")
      (value "LM3914N")
      (footprint "eagle-import:DIL18")
      (libsource (lib "eagle-import") (part "LM3914N"))
    )
    (comp (ref "R68")
      (value "1k2")
      (footprint "eagle-import:0207_7")
      (libsource (lib "eagle-import") (part "resistor_348_R-EU_0207/7"))
    )
    (comp (ref "R69")
      (value "1k2")
      (footprint "eagle-import:0207_7")
      (libsource (lib "eagle-import") (part "resistor_348_R-EU_0207/7"))
    )
  )
  (nets
    (net (code "1") (name "GND") (class "Default")
      (node (ref "C12") (pin "-") (pinfunction "-_-") (pintype "passive"))
      (node (ref "C13") (pin "-") (pinfunction "-_-") (pintype "passive"))
      (node (ref "C22") (pin "-") (pinfunction "-_-") (pintype "passive"))
      (node (ref "C23") (pin "-") (pinfunction "-_-") (pintype "passive"))
      (node (ref "C24") (pin "-") (pinfunction "-_-") (pintype "passive"))
      (node (ref "C25") (pin "-") (pinfunction "-_-") (pintype "passive"))
      (node (ref "C34") (pin "-") (pinfunction "-_-") (pintype "passive"))
      (node (ref "C35") (pin "-") (pinfunction "-_-") (pintype "passive"))
      (node (ref "C36") (pin "-") (pinfunction "-_-") (pintype "passive"))
      (node (ref "C37") (pin "-") (pinfunction "-_-") (pintype "passive"))
      (node (ref "C38") (pin "2") (pinfunction "2_2") (pintype "passive"))
      (node (ref "C39") (pin "2") (pinfunction "2_2") (pintype "passive"))
      (node (ref "C40") (pin "2") (pinfunction "2_2") (pintype "passive"))
      (node (ref "C41") (pin "2") (pinfunction "2_2") (pintype "passive"))
      (node (ref "C42") (pin "2") (pinfunction "2_2") (pintype "passive"))
      (node (ref "C43") (pin "2") (pinfunction "2_2") (pintype "passive"))
      (node (ref "C44") (pin "2") (pinfunction "2_2") (pintype "passive"))
      (node (ref "C45") (pin "2") (pinfunction "2_2") (pintype "passive"))
      (node (ref "C46") (pin "2") (pinfunction "2_2") (pintype "passive"))
      (node (ref "C47") (pin "2") (pinfunction "2_2") (pintype "passive"))
      (node (ref "C5") (pin "2") (pinfunction "2_2") (pintype "passive"))
      (node (ref "C6") (pin "2") (pinfunction "2_2") (pintype "passive"))
      (node (ref "C7") (pin "2") (pinfunction "2_2") (pintype "passive"))
      (node (ref "D7") (pin "C") (pinfunction "C_C") (pintype "passive"))
      (node (ref "IC1") (pin "11") (pinfunction "V-_11") (pintype "power_in"))
      (node (ref "IC10") (pin "2") (pinfunction "V-_2") (pintype "power_in"))
      (node (ref "IC10") (pin "8") (pinfunction "ADJ_8") (pintype "input"))
      (node (ref "IC11") (pin "2") (pinfunction "V-_2") (pintype "power_in"))
      (node (ref "IC11") (pin "8") (pinfunction "ADJ_8") (pintype "input"))
      (node (ref "IC12") (pin "2") (pinfunction "V-_2") (pintype "power_in"))
      (node (ref "IC12") (pin "8") (pinfunction "ADJ_8") (pintype "input"))
      (node (ref "IC13") (pin "2") (pinfunction "V-_2") (pintype "power_in"))
      (node (ref "IC13") (pin "8") (pinfunction "ADJ_8") (pintype "input"))
      (node (ref "IC2") (pin "11") (pinfunction "V-_11") (pintype "power_in"))
      (node (ref "IC3") (pin "11") (pinfunction "V-_11") (pintype "power_in"))
      (node (ref "IC4") (pin "2") (pinfunction "V-_2") (pintype "power_in"))
      (node (ref "IC4") (pin "8") (pinfunction "ADJ_8") (pintype "input"))
      (node (ref "IC5") (pin "2") (pinfunction "V-_2") (pintype "power_in"))
      (node (ref "IC5") (pin "8") (pinfunction "ADJ_8") (pintype "input"))
      (node (ref "IC6") (pin "2") (pinfunction "V-_2") (pintype "power_in"))
      (node (ref "IC6") (pin "8") (pinfunction "ADJ_8") (pintype "input"))
      (node (ref "IC7") (pin "2") (pinfunction "V-_2") (pintype "power_in"))
      (node (ref "IC7") (pin "8") (pinfunction "ADJ_8") (pintype "input"))
      (node (ref "IC8") (pin "2") (pinfunction "V-_2") (pintype "power_in"))
      (node (ref "IC8") (pin "8") (pinfunction "ADJ_8") (pintype "input"))
      (node (ref "IC9") (pin "2") (pinfunction "V-_2") (pintype "power_in"))
      (node (ref "IC9") (pin "8") (pinfunction "ADJ_8") (pintype "input"))
      (node (ref "J1") (pin "1") (pinfunction "GND_1") (pintype "power_in"))
      (node (ref "J1") (pin "4") (pinfunction "CLMP_4") (pintype "bidirectional"))
      (node (ref "J2") (pin "2") (pinfunction "2_2") (pintype "passive"))
      (node (ref "J2") (pin "3") (pinfunction "3_3") (pintype "passive"))
      (node (ref "Q1") (pin "-") (pinfunction "1_-") (pintype "passive"))
      (node (ref "R10") (pin "1") (pinfunction "1_1") (pintype "passive"))
      (node (ref "R14") (pin "1") (pinfunction "1_1") (pintype "passive"))
      (node (ref "R17") (pin "1") (pinfunction "1_1") (pintype "passive"))
      (node (ref "R18") (pin "1") (pinfunction "1_1") (pintype "passive"))
      (node (ref "R22") (pin "1") (pinfunction "1_1") (pintype "passive"))
      (node (ref "R23") (pin "1") (pinfunction "1_1") (pintype "passive"))
      (node (ref "R28") (pin "1") (pinfunction "1_1") (pintype "passive"))
      (node (ref "R29") (pin "1") (pinfunction "1_1") (pintype "passive"))
      (node (ref "R30") (pin "1") (pinfunction "1_1") (pintype "passive"))
      (node (ref "R31") (pin "1") (pinfunction "1_1") (pintype "passive"))
      (node (ref "R36") (pin "1") (pinfunction "1_1") (pintype "passive"))
      (node (ref "R37") (pin "1") (pinfunction "1_1") (pintype "passive"))
      (node (ref "R38") (pin "1") (pinfunction "1_1") (pintype "passive"))
      (node (ref "R39") (pin "1") (pinfunction "1_1") (pintype "passive"))
      (node (ref "R4") (pin "2") (pinfunction "S_2") (pintype "passive"))
      (node (ref "R44") (pin "1") (pinfunction "1_1") (pintype "passive"))
      (node (ref "R45") (pin "1") (pinfunction "1_1") (pintype "passive"))
      (node (ref "R46") (pin "1") (pinfunction "1_1") (pintype "passive"))
      (node (ref "R47") (pin "1") (pinfunction "1_1") (pintype "passive"))
      (node (ref "R5") (pin "2") (pinfunction "S_2") (pintype "passive"))
      (node (ref "R52") (pin "1") (pinfunction "1_1") (pintype "passive"))
      (node (ref "R53") (pin "1") (pinfunction "1_1") (pintype "passive"))
      (node (ref "R54") (pin "1") (pinfunction "1_1") (pintype "passive"))
      (node (ref "R55") (pin "1") (pinfunction "1_1") (pintype "passive"))
      (node (ref "R57") (pin "1") (pinfunction "1_1") (pintype "passive"))
      (node (ref "R59") (pin "1") (pinfunction "1_1") (pintype "passive"))
      (node (ref "R60") (pin "1") (pinfunction "1_1") (pintype "passive"))
      (node (ref "R61") (pin "1") (pinfunction "1_1") (pintype "passive"))
      (node (ref "R62") (pin "1") (pinfunction "1_1") (pintype "passive"))
      (node (ref "R63") (pin "1") (pinfunction "1_1") (pintype "passive"))
      (node (ref "R64") (pin "1") (pinfunction "1_1") (pintype "passive"))
      (node (ref "R65") (pin "1") (pinfunction "1_1") (pintype "passive"))
      (node (ref "R66") (pin "1") (pinfunction "1_1") (pintype "passive"))
      (node (ref "R67") (pin "1") (pinfunction "1_1") (pintype "passive"))
      (node (ref "R68") (pin "1") (pinfunction "1_1") (pintype "passive"))
      (node (ref "R69") (pin "1") (pinfunction "1_1") (pintype "passive"))
      (node (ref "R7") (pin "1") (pinfunction "1_1") (pintype "passive"))
      (node (ref "TP2") (pin "TP") (pinfunction "TP_TP") (pintype "input"))
    )
    (net (code "2") (name "Net-(C2-Pad-)") (class "Default")
      (node (ref "C2") (pin "-") (pinfunction "-_-") (pintype "passive"))
      (node (ref "R8") (pin "2") (pinfunction "2_2") (pintype "passive"))
    )
    (net (code "3") (name "Net-(C3-Pad-)") (class "Default")
      (node (ref "C3") (pin "-") (pinfunction "-_-") (pintype "passive"))
      (node (ref "R11") (pin "2") (pinfunction "2_2") (pintype "passive"))
    )
    (net (code "4") (name "Net-(C4-Pad+)") (class "Default")
      (node (ref "C4") (pin "+") (pinfunction "+_+") (pintype "passive"))
      (node (ref "S1") (pin "2") (pinfunction "2_2") (pintype "passive"))
    )
    (net (code "5") (name "Net-(C10-Pad1)") (class "Default")
      (node (ref "C10") (pin "1") (pinfunction "1_1") (pintype "passive"))
      (node (ref "C8") (pin "1") (pinfunction "1_1") (pintype "passive"))
      (node (ref "R15") (pin "2") (pinfunction "2_2") (pintype "passive"))
      (node (ref "R17") (pin "2") (pinfunction "2_2") (pintype "passive"))
    )
    (net (code "6") (name "Net-(C11-Pad1)") (class "Default")
      (node (ref "C11") (pin "1") (pinfunction "1_1") (pintype "passive"))
      (node (ref "C9") (pin "1") (pinfunction "1_1") (pintype "passive"))
      (node (ref "R16") (pin "2") (pinfunction "2_2") (pintype "passive"))
      (node (ref "R18") (pin "2") (pinfunction "2_2") (pintype "passive"))
    )
    (net (code "7") (name "Net-(C14-Pad1)") (class "Default")
      (node (ref "C14") (pin "1") (pinfunction "1_1") (pintype "passive"))
      (node (ref "C18") (pin "1") (pinfunction "1_1") (pintype "passive"))
      (node (ref "R24") (pin "2") (pinfunction "2_2") (pintype "passive"))
      (node (ref "R28") (pin "2") (pinfunction "2_2") (pintype "passive"))
    )
    (net (code "8") (name "Net-(C15-Pad1)") (class "Default")
      (node (ref "C15") (pin "1") (pinfunction "1_1") (pintype "passive"))
      (node (ref "C19") (pin "1") (pinfunction "1_1") (pintype "passive"))
      (node (ref "R25") (pin "2") (pinfunction "2_2") (pintype "passive"))
      (node (ref "R29") (pin "2") (pinfunction "2_2") (pintype "passive"))
    )
    (net (code "9") (name "Net-(C16-Pad1)") (class "Default")
      (node (ref "C16") (pin "1") (pinfunction "1_1") (pintype "passive"))
      (node (ref "C20") (pin "1") (pinfunction "1_1") (pintype "passive"))
      (node (ref "R26") (pin "2") (pinfunction "2_2") (pintype "passive"))
      (node (ref "R30") (pin "2") (pinfunction "2_2") (pintype "passive"))
    )
    (net (code "10") (name "Net-(C17-Pad1)") (class "Default")
      (node (ref "C17") (pin "1") (pinfunction "1_1") (pintype "passive"))
      (node (ref "C21") (pin "1") (pinfunction "1_1") (pintype "passive"))
      (node (ref "R27") (pin "2") (pinfunction "2_2") (pintype "passive"))
      (node (ref "R31") (pin "2") (pinfunction "2_2") (pintype "passive"))
    )
    (net (code "11") (name "Net-(C26-Pad1)") (class "Default")
      (node (ref "C26") (pin "1") (pinfunction "1_1") (pintype "passive"))
      (node (ref "C30") (pin "1") (pinfunction "1_1") (pintype "passive"))
      (node (ref "R40") (pin "2") (pinfunction "2_2") (pintype "passive"))
      (node (ref "R44") (pin "2") (pinfunction "2_2") (pintype "passive"))
    )
    (net (code "12") (name "Net-(C27-Pad1)") (class "Default")
      (node (ref "C27") (pin "1") (pinfunction "1_1") (pintype "passive"))
      (node (ref "C31") (pin "1") (pinfunction "1_1") (pintype "passive"))
      (node (ref "R41") (pin "2") (pinfunction "2_2") (pintype "passive"))
      (node (ref "R45") (pin "2") (pinfunction "2_2") (pintype "passive"))
    )
    (net (code "13") (name "Net-(C28-Pad1)") (class "Default")
      (node (ref "C28") (pin "1") (pinfunction "1_1") (pintype "passive"))
      (node (ref "C32") (pin "1") (pinfunction "1_1") (pintype "passive"))
      (node (ref "R42") (pin "2") (pinfunction "2_2") (pintype "passive"))
      (node (ref "R46") (pin "2") (pinfunction "2_2") (pintype "passive"))
    )
    (net (code "14") (name "Net-(C29-Pad1)") (class "Default")
      (node (ref "C29") (pin "1") (pinfunction "1_1") (pintype "passive"))
      (node (ref "C33") (pin "1") (pinfunction "1_1") (pintype "passive"))
      (node (ref "R43") (pin "2") (pinfunction "2_2") (pintype "passive"))
      (node (ref "R47") (pin "2") (pinfunction "2_2") (pintype "passive"))
    )
    (net (code "15") (name "Net-(IC1A-+IN)") (class "Default")
      (node (ref "C1") (pin "+") (pinfunction "+_+") (pintype "passive"))
      (node (ref "IC1") (pin "3") (pinfunction "+IN_3") (pintype "input"))
      (node (ref "R6") (pin "1") (pinfunction "1_1") (pintype "passive"))
      (node (ref "R7") (pin "2") (pinfunction "2_2") (pintype "passive"))
    )
    (net (code "16") (name "Net-(IC1A--IN)") (class "Default")
      (node (ref "C2") (pin "+") (pinfunction "+_+") (pintype "passive"))
      (node (ref "IC1") (pin "2") (pinfunction "-IN_2") (pintype "input"))
      (node (ref "R12") (pin "1") (pinfunction "1_1") (pintype "passive"))
    )
    (net (code "17") (name "Net-(IC1A-OUT)") (class "Default")
      (node (ref "IC1") (pin "1") (pinfunction "OUT_1") (pintype "output"))
      (node (ref "R12") (pin "2") (pinfunction "2_2") (pintype "passive"))
      (node (ref "S1") (pin "1") (pinfunction "1_1") (pintype "passive"))
    )
    (net (code "18") (name "Net-(IC1B-+IN)") (class "Default")
      (node (ref "IC1") (pin "5") (pinfunction "+IN_5") (pintype "input"))
      (node (ref "R10") (pin "2") (pinfunction "2_2") (pintype "passive"))
      (node (ref "R2") (pin "2") (pinfunction "2_2") (pintype "passive"))
      (node (ref "R3") (pin "2") (pinfunction "2_2") (pintype "passive"))
      (node (ref "R9") (pin "1") (pinfunction "1_1") (pintype "passive"))
    )
    (net (code "19") (name "Net-(IC1B--IN)") (class "Default")
      (node (ref "C3") (pin "+") (pinfunction "+_+") (pintype "passive"))
      (node (ref "IC1") (pin "6") (pinfunction "-IN_6") (pintype "input"))
      (node (ref "R13") (pin "1") (pinfunction "1_1") (pintype "passive"))
    )
    (net (code "20") (name "Net-(IC1B-OUT)") (class "Default")
      (node (ref "IC1") (pin "7") (pinfunction "OUT_7") (pintype "output"))
      (node (ref "R13") (pin "2") (pinfunction "2_2") (pintype "passive"))
      (node (ref "S1") (pin "3") (pinfunction "3_3") (pintype "passive"))
    )
    (net (code "21") (name "Net-(IC1C--IN)") (class "Default")
      (node (ref "C8") (pin "2") (pinfunction "2_2") (pintype "passive"))
      (node (ref "IC1") (pin "9") (pinfunction "-IN_9") (pintype "input"))
      (node (ref "R20") (pin "1") (pinfunction "1_1") (pintype "passive"))
    )
    (net (code "22") (name "Net-(IC1C-OUT)") (class "Default")
      (node (ref "C10") (pin "2") (pinfunction "2_2") (pintype "passive"))
      (node (ref "D1") (pin "A") (pinfunction "A_A") (pintype "passive"))
      (node (ref "IC1") (pin "8") (pinfunction "OUT_8") (pintype "output"))
      (node (ref "R20") (pin "2") (pinfunction "2_2") (pintype "passive"))
    )
    (net (code "23") (name "Net-(IC1D--IN)") (class "Default")
      (node (ref "C9") (pin "2") (pinfunction "2_2") (pintype "passive"))
      (node (ref "IC1") (pin "13") (pinfunction "-IN_13") (pintype "input"))
      (node (ref "R21") (pin "1") (pinfunction "1_1") (pintype "passive"))
    )
    (net (code "24") (name "Net-(IC1D-OUT)") (class "Default")
      (node (ref "C11") (pin "2") (pinfunction "2_2") (pintype "passive"))
      (node (ref "D2") (pin "A") (pinfunction "A_A") (pintype "passive"))
      (node (ref "IC1") (pin "14") (pinfunction "OUT_14") (pintype "output"))
      (node (ref "R21") (pin "2") (pinfunction "2_2") (pintype "passive"))
    )
    (net (code "25") (name "Net-(IC2A--IN)") (class "Default")
      (node (ref "C14") (pin "2") (pinfunction "2_2") (pintype "passive"))
      (node (ref "IC2") (pin "2") (pinfunction "-IN_2") (pintype "input"))
      (node (ref "R32") (pin "1") (pinfunction "1_1") (pintype "passive"))
    )
    (net (code "26") (name "Net-(IC2A-OUT)") (class "Default")
      (node (ref "C18") (pin "2") (pinfunction "2_2") (pintype "passive"))
      (node (ref "D3") (pin "A") (pinfunction "A_A") (pintype "passive"))
      (node (ref "IC2") (pin "1") (pinfunction "OUT_1") (pintype "output"))
      (node (ref "R32") (pin "2") (pinfunction "2_2") (pintype "passive"))
    )
    (net (code "27") (name "Net-(IC2B--IN)") (class "Default")
      (node (ref "C15") (pin "2") (pinfunction "2_2") (pintype "passive"))
      (node (ref "IC2") (pin "6") (pinfunction "-IN_6") (pintype "input"))
      (node (ref "R33") (pin "1") (pinfunction "1_1") (pintype "passive"))
    )
    (net (code "28") (name "Net-(IC2B-OUT)") (class "Default")
      (node (ref "C19") (pin "2") (pinfunction "2_2") (pintype "passive"))
      (node (ref "D4") (pin "A") (pinfunction "A_A") (pintype "passive"))
      (node (ref "IC2") (pin "7") (pinfunction "OUT_7") (pintype "output"))
      (node (ref "R33") (pin "2") (pinfunction "2_2") (pintype "passive"))
    )
    (net (code "29") (name "Net-(IC2C--IN)") (class "Default")
      (node (ref "C16") (pin "2") (pinfunction "2_2") (pintype "passive"))
      (node (ref "IC2") (pin "9") (pinfunction "-IN_9") (pintype "input"))
      (node (ref "R34") (pin "1") (pinfunction "1_1") (pintype "passive"))
    )
    (net (code "30") (name "Net-(IC2C-OUT)") (class "Default")
      (node (ref "C20") (pin "2") (pinfunction "2_2") (pintype "passive"))
      (node (ref "D5") (pin "A") (pinfunction "A_A") (pintype "passive"))
      (node (ref "IC2") (pin "8") (pinfunction "OUT_8") (pintype "output"))
      (node (ref "R34") (pin "2") (pinfunction "2_2") (pintype "passive"))
    )
    (net (code "31") (name "Net-(IC2D--IN)") (class "Default")
      (node (ref "C17") (pin "2") (pinfunction "2_2") (pintype "passive"))
      (node (ref "IC2") (pin "13") (pinfunction "-IN_13") (pintype "input"))
      (node (ref "R35") (pin "1") (pinfunction "1_1") (pintype "passive"))
    )
    (net (code "32") (name "Net-(IC2D-OUT)") (class "Default")
      (node (ref "C21") (pin "2") (pinfunction "2_2") (pintype "passive"))
      (node (ref "D6") (pin "A") (pinfunction "A_A") (pintype "passive"))
      (node (ref "IC2") (pin "14") (pinfunction "OUT_14") (pintype "output"))
      (node (ref "R35") (pin "2") (pinfunction "2_2") (pintype "passive"))
    )
    (net (code "33") (name "Net-(IC3A--IN)") (class "Default")
      (node (ref "C26") (pin "2") (pinfunction "2_2") (pintype "passive"))
      (node (ref "IC3") (pin "2") (pinfunction "-IN_2") (pintype "input"))
      (node (ref "R48") (pin "1") (pinfunction "1_1") (pintype "passive"))
    )
    (net (code "34") (name "Net-(IC3A-OUT)") (class "Default")
      (node (ref "C30") (pin "2") (pinfunction "2_2") (pintype "passive"))
      (node (ref "D8") (pin "A") (pinfunction "A_A") (pintype "passive"))
      (node (ref "IC3") (pin "1") (pinfunction "OUT_1") (pintype "output"))
      (node (ref "R48") (pin "2") (pinfunction "2_2") (pintype "passive"))
    )
    (net (code "35") (name "Net-(IC3B--IN)") (class "Default")
      (node (ref "C27") (pin "2") (pinfunction "2_2") (pintype "passive"))
      (node (ref "IC3") (pin "6") (pinfunction "-IN_6") (pintype "input"))
      (node (ref "R49") (pin "1") (pinfunction "1_1") (pintype "passive"))
    )
    (net (code "36") (name "Net-(IC3B-OUT)") (class "Default")
      (node (ref "C31") (pin "2") (pinfunction "2_2") (pintype "passive"))
      (node (ref "D9") (pin "A") (pinfunction "A_A") (pintype "passive"))
      (node (ref "IC3") (pin "7") (pinfunction "OUT_7") (pintype "output"))
      (node (ref "R49") (pin "2") (pinfunction "2_2") (pintype "passive"))
    )
    (net (code "37") (name "Net-(IC3C--IN)") (class "Default")
      (node (ref "C28") (pin "2") (pinfunction "2_2") (pintype "passive"))
      (node (ref "IC3") (pin "9") (pinfunction "-IN_9") (pintype "input"))
      (node (ref "R50") (pin "1") (pinfunction "1_1") (pintype "passive"))
    )
    (net (code "38") (name "Net-(IC3C-OUT)") (class "Default")
      (node (ref "C32") (pin "2") (pinfunction "2_2") (pintype "passive"))
      (node (ref "D10") (pin "A") (pinfunction "A_A") (pintype "passive"))
      (node (ref "IC3") (pin "8") (pinfunction "OUT_8") (pintype "output"))
      (node (ref "R50") (pin "2") (pinfunction "2_2") (pintype "passive"))
    )
    (net (code "39") (name "Net-(IC3D--IN)") (class "Default")
      (node (ref "C29") (pin "2") (pinfunction "2_2") (pintype "passive"))
      (node (ref "IC3") (pin "13") (pinfunction "-IN_13") (pintype "input"))
      (node (ref "R51") (pin "1") (pinfunction "1_1") (pintype "passive"))
    )
    (net (code "40") (name "Net-(IC3D-OUT)") (class "Default")
      (node (ref "C33") (pin "2") (pinfunction "2_2") (pintype "passive"))
      (node (ref "D11") (pin "A") (pinfunction "A_A") (pintype "passive"))
      (node (ref "IC3") (pin "14") (pinfunction "OUT_14") (pintype "output"))
      (node (ref "R51") (pin "2") (pinfunction "2_2") (pintype "passive"))
    )
    (net (code "41") (name "Net-(IC4-L1)") (class "Default")
      (node (ref "DIS1") (pin "11") (pinfunction "11_11") (pintype "bidirectional"))
      (node (ref "IC4") (pin "1") (pinfunction "L1_1") (pintype "output"))
    )
    (net (code "42") (name "Net-(IC4-L2)") (class "Default")
      (node (ref "DIS1") (pin "12") (pinfunction "12_12") (pintype "bidirectional"))
      (node (ref "IC4") (pin "18") (pinfunction "L2_18") (pintype "output"))
    )
    (net (code "43") (name "Net-(IC4-L3)") (class "Default")
      (node (ref "DIS1") (pin "13") (pinfunction "13_13") (pintype "bidirectional"))
      (node (ref "IC4") (pin "17") (pinfunction "L3_17") (pintype "output"))
    )
    (net (code "44") (name "Net-(IC4-L4)") (class "Default")
      (node (ref "DIS1") (pin "14") (pinfunction "14_14") (pintype "bidirectional"))
      (node (ref "IC4") (pin "16") (pinfunction "L4_16") (pintype "output"))
    )
    (net (code "45") (name "Net-(IC4-L5)") (class "Default")
      (node (ref "DIS1") (pin "15") (pinfunction "15_15") (pintype "bidirectional"))
      (node (ref "IC4") (pin "15") (pinfunction "L5_15") (pintype "output"))
    )
    (net (code "46") (name "Net-(IC4-L6)") (class "Default")
      (node (ref "DIS1") (pin "16") (pinfunction "16_16") (pintype "bidirectional"))
      (node (ref "IC4") (pin "14") (pinfunction "L6_14") (pintype "output"))
    )
    (net (code "47") (name "Net-(IC4-L7)") (class "Default")
      (node (ref "DIS1") (pin "17") (pinfunction "17_17") (pintype "bidirectional"))
      (node (ref "IC4") (pin "13") (pinfunction "L7_13") (pintype "output"))
    )
    (net (code "48") (name "Net-(IC4-L8)") (class "Default")
      (node (ref "DIS1") (pin "18") (pinfunction "18_18") (pintype "bidirectional"))
      (node (ref "IC4") (pin "12") (pinfunction "L8_12") (pintype "output"))
    )
    (net (code "49") (name "Net-(IC4-L9)") (class "Default")
      (node (ref "DIS1") (pin "19") (pinfunction "19_19") (pintype "bidirectional"))
      (node (ref "IC4") (pin "11") (pinfunction "L9_11") (pintype "output"))
    )
    (net (code "50") (name "Net-(IC4-L10)") (class "Default")
      (node (ref "DIS1") (pin "20") (pinfunction "20_20") (pintype "bidirectional"))
      (node (ref "IC4") (pin "10") (pinfunction "L10_10") (pintype "output"))
    )
    (net (code "51") (name "Net-(IC4-VR)") (class "Default")
      (node (ref "IC4") (pin "7") (pinfunction "VR_7") (pintype "output"))
      (node (ref "R60") (pin "2") (pinfunction "2_2") (pintype "passive"))
    )
    (net (code "52") (name "Net-(IC5-L1)") (class "Default")
      (node (ref "DIS2") (pin "11") (pinfunction "11_11") (pintype "bidirectional"))
      (node (ref "IC5") (pin "1") (pinfunction "L1_1") (pintype "output"))
    )
    (net (code "53") (name "Net-(IC5-L2)") (class "Default")
      (node (ref "DIS2") (pin "12") (pinfunction "12_12") (pintype "bidirectional"))
      (node (ref "IC5") (pin "18") (pinfunction "L2_18") (pintype "output"))
    )
    (net (code "54") (name "Net-(IC5-L3)") (class "Default")
      (node (ref "DIS2") (pin "13") (pinfunction "13_13") (pintype "bidirectional"))
      (node (ref "IC5") (pin "17") (pinfunction "L3_17") (pintype "output"))
    )
    (net (code "55") (name "Net-(IC5-L4)") (class "Default")
      (node (ref "DIS2") (pin "14") (pinfunction "14_14") (pintype "bidirectional"))
      (node (ref "IC5") (pin "16") (pinfunction "L4_16") (pintype "output"))
    )
    (net (code "56") (name "Net-(IC5-L5)") (class "Default")
      (node (ref "DIS2") (pin "15") (pinfunction "15_15") (pintype "bidirectional"))
      (node (ref "IC5") (pin "15") (pinfunction "L5_15") (pintype "output"))
    )
    (net (code "57") (name "Net-(IC5-L6)") (class "Default")
      (node (ref "DIS2") (pin "16") (pinfunction "16_16") (pintype "bidirectional"))
      (node (ref "IC5") (pin "14") (pinfunction "L6_14") (pintype "output"))
    )
    (net (code "58") (name "Net-(IC5-L7)") (class "Default")
      (node (ref "DIS2") (pin "17") (pinfunction "17_17") (pintype "bidirectional"))
      (node (ref "IC5") (pin "13") (pinfunction "L7_13") (pintype "output"))
    )
    (net (code "59") (name "Net-(IC5-L8)") (class "Default")
      (node (ref "DIS2") (pin "18") (pinfunction "18_18") (pintype "bidirectional"))
      (node (ref "IC5") (pin "12") (pinfunction "L8_12") (pintype "output"))
    )
    (net (code "60") (name "Net-(IC5-L9)") (class "Default")
      (node (ref "DIS2") (pin "19") (pinfunction "19_19") (pintype "bidirectional"))
      (node (ref "IC5") (pin "11") (pinfunction "L9_11") (pintype "output"))
    )
    (net (code "61") (name "Net-(IC5-L10)") (class "Default")
      (node (ref "DIS2") (pin "20") (pinfunction "20_20") (pintype "bidirectional"))
      (node (ref "IC5") (pin "10") (pinfunction "L10_10") (pintype "output"))
    )
    (net (code "62") (name "Net-(IC5-VR)") (class "Default")
      (node (ref "IC5") (pin "7") (pinfunction "VR_7") (pintype "output"))
      (node (ref "R61") (pin "2") (pinfunction "2_2") (pintype "passive"))
    )
    (net (code "63") (name "Net-(IC6-L1)") (class "Default")
      (node (ref "DIS3") (pin "11") (pinfunction "11_11") (pintype "bidirectional"))
      (node (ref "IC6") (pin "1") (pinfunction "L1_1") (pintype "output"))
    )
    (net (code "64") (name "Net-(IC6-L2)") (class "Default")
      (node (ref "DIS3") (pin "12") (pinfunction "12_12") (pintype "bidirectional"))
      (node (ref "IC6") (pin "18") (pinfunction "L2_18") (pintype "output"))
    )
    (net (code "65") (name "Net-(IC6-L3)") (class "Default")
      (node (ref "DIS3") (pin "13") (pinfunction "13_13") (pintype "bidirectional"))
      (node (ref "IC6") (pin "17") (pinfunction "L3_17") (pintype "output"))
    )
    (net (code "66") (name "Net-(IC6-L4)") (class "Default")
      (node (ref "DIS3") (pin "14") (pinfunction "14_14") (pintype "bidirectional"))
      (node (ref "IC6") (pin "16") (pinfunction "L4_16") (pintype "output"))
    )
    (net (code "67") (name "Net-(IC6-L5)") (class "Default")
      (node (ref "DIS3") (pin "15") (pinfunction "15_15") (pintype "bidirectional"))
      (node (ref "IC6") (pin "15") (pinfunction "L5_15") (pintype "output"))
    )
    (net (code "68") (name "Net-(IC6-L6)") (class "Default")
      (node (ref "DIS3") (pin "16") (pinfunction "16_16") (pintype "bidirectional"))
      (node (ref "IC6") (pin "14") (pinfunction "L6_14") (pintype "output"))
    )
    (net (code "69") (name "Net-(IC6-L7)") (class "Default")
      (node (ref "DIS3") (pin "17") (pinfunction "17_17") (pintype "bidirectional"))
      (node (ref "IC6") (pin "13") (pinfunction "L7_13") (pintype "output"))
    )
    (net (code "70") (name "Net-(IC6-L8)") (class "Default")
      (node (ref "DIS3") (pin "18") (pinfunction "18_18") (pintype "bidirectional"))
      (node (ref "IC6") (pin "12") (pinfunction "L8_12") (pintype "output"))
    )
    (net (code "71") (name "Net-(IC6-L9)") (class "Default")
      (node (ref "DIS3") (pin "19") (pinfunction "19_19") (pintype "bidirectional"))
      (node (ref "IC6") (pin "11") (pinfunction "L9_11") (pintype "output"))
    )
    (net (code "72") (name "Net-(IC6-L10)") (class "Default")
      (node (ref "DIS3") (pin "20") (pinfunction "20_20") (pintype "bidirectional"))
      (node (ref "IC6") (pin "10") (pinfunction "L10_10") (pintype "output"))
    )
    (net (code "73") (name "Net-(IC6-VR)") (class "Default")
      (node (ref "IC6") (pin "7") (pinfunction "VR_7") (pintype "output"))
      (node (ref "R62") (pin "2") (pinfunction "2_2") (pintype "passive"))
    )
    (net (code "74") (name "Net-(IC7-L1)") (class "Default")
      (node (ref "DIS4") (pin "11") (pinfunction "11_11") (pintype "bidirectional"))
      (node (ref "IC7") (pin "1") (pinfunction "L1_1") (pintype "output"))
    )
    (net (code "75") (name "Net-(IC7-L2)") (class "Default")
      (node (ref "DIS4") (pin "12") (pinfunction "12_12") (pintype "bidirectional"))
      (node (ref "IC7") (pin "18") (pinfunction "L2_18") (pintype "output"))
    )
    (net (code "76") (name "Net-(IC7-L3)") (class "Default")
      (node (ref "DIS4") (pin "13") (pinfunction "13_13") (pintype "bidirectional"))
      (node (ref "IC7") (pin "17") (pinfunction "L3_17") (pintype "output"))
    )
    (net (code "77") (name "Net-(IC7-L4)") (class "Default")
      (node (ref "DIS4") (pin "14") (pinfunction "14_14") (pintype "bidirectional"))
      (node (ref "IC7") (pin "16") (pinfunction "L4_16") (pintype "output"))
    )
    (net (code "78") (name "Net-(IC7-L5)") (class "Default")
      (node (ref "DIS4") (pin "15") (pinfunction "15_15") (pintype "bidirectional"))
      (node (ref "IC7") (pin "15") (pinfunction "L5_15") (pintype "output"))
    )
    (net (code "79") (name "Net-(IC7-L6)") (class "Default")
      (node (ref "DIS4") (pin "16") (pinfunction "16_16") (pintype "bidirectional"))
      (node (ref "IC7") (pin "14") (pinfunction "L6_14") (pintype "output"))
    )
    (net (code "80") (name "Net-(IC7-L7)") (class "Default")
      (node (ref "DIS4") (pin "17") (pinfunction "17_17") (pintype "bidirectional"))
      (node (ref "IC7") (pin "13") (pinfunction "L7_13") (pintype "output"))
    )
    (net (code "81") (name "Net-(IC7-L8)") (class "Default")
      (node (ref "DIS4") (pin "18") (pinfunction "18_18") (pintype "bidirectional"))
      (node (ref "IC7") (pin "12") (pinfunction "L8_12") (pintype "output"))
    )
    (net (code "82") (name "Net-(IC7-L9)") (class "Default")
      (node (ref "DIS4") (pin "19") (pinfunction "19_19") (pintype "bidirectional"))
      (node (ref "IC7") (pin "11") (pinfunction "L9_11") (pintype "output"))
    )
    (net (code "83") (name "Net-(IC7-L10)") (class "Default")
      (node (ref "DIS4") (pin "20") (pinfunction "20_20") (pintype "bidirectional"))
      (node (ref "IC7") (pin "10") (pinfunction "L10_10") (pintype "output"))
    )
    (net (code "84") (name "Net-(IC7-VR)") (class "Default")
      (node (ref "IC7") (pin "7") (pinfunction "VR_7") (pintype "output"))
      (node (ref "R63") (pin "2") (pinfunction "2_2") (pintype "passive"))
    )
    (net (code "85") (name "Net-(IC8-L1)") (class "Default")
      (node (ref "DIS5") (pin "11") (pinfunction "11_11") (pintype "bidirectional"))
      (node (ref "IC8") (pin "1") (pinfunction "L1_1") (pintype "output"))
    )
    (net (code "86") (name "Net-(IC8-L2)") (class "Default")
      (node (ref "DIS5") (pin "12") (pinfunction "12_12") (pintype "bidirectional"))
      (node (ref "IC8") (pin "18") (pinfunction "L2_18") (pintype "output"))
    )
    (net (code "87") (name "Net-(IC8-L3)") (class "Default")
      (node (ref "DIS5") (pin "13") (pinfunction "13_13") (pintype "bidirectional"))
      (node (ref "IC8") (pin "17") (pinfunction "L3_17") (pintype "output"))
    )
    (net (code "88") (name "Net-(IC8-L4)") (class "Default")
      (node (ref "DIS5") (pin "14") (pinfunction "14_14") (pintype "bidirectional"))
      (node (ref "IC8") (pin "16") (pinfunction "L4_16") (pintype "output"))
    )
    (net (code "89") (name "Net-(IC8-L5)") (class "Default")
      (node (ref "DIS5") (pin "15") (pinfunction "15_15") (pintype "bidirectional"))
      (node (ref "IC8") (pin "15") (pinfunction "L5_15") (pintype "output"))
    )
    (net (code "90") (name "Net-(IC8-L6)") (class "Default")
      (node (ref "DIS5") (pin "16") (pinfunction "16_16") (pintype "bidirectional"))
      (node (ref "IC8") (pin "14") (pinfunction "L6_14") (pintype "output"))
    )
    (net (code "91") (name "Net-(IC8-L7)") (class "Default")
      (node (ref "DIS5") (pin "17") (pinfunction "17_17") (pintype "bidirectional"))
      (node (ref "IC8") (pin "13") (pinfunction "L7_13") (pintype "output"))
    )
    (net (code "92") (name "Net-(IC8-L8)") (class "Default")
      (node (ref "DIS5") (pin "18") (pinfunction "18_18") (pintype "bidirectional"))
      (node (ref "IC8") (pin "12") (pinfunction "L8_12") (pintype "output"))
    )
    (net (code "93") (name "Net-(IC8-L9)") (class "Default")
      (node (ref "DIS5") (pin "19") (pinfunction "19_19") (pintype "bidirectional"))
      (node (ref "IC8") (pin "11") (pinfunction "L9_11") (pintype "output"))
    )
    (net (code "94") (name "Net-(IC8-L10)") (class "Default")
      (node (ref "DIS5") (pin "20") (pinfunction "20_20") (pintype "bidirectional"))
      (node (ref "IC8") (pin "10") (pinfunction "L10_10") (pintype "output"))
    )
    (net (code "95") (name "Net-(IC8-VR)") (class "Default")
      (node (ref "IC8") (pin "7") (pinfunction "VR_7") (pintype "output"))
      (node (ref "R64") (pin "2") (pinfunction "2_2") (pintype "passive"))
    )
    (net (code "96") (name "Net-(IC9-L1)") (class "Default")
      (node (ref "DIS6") (pin "11") (pinfunction "11_11") (pintype "bidirectional"))
      (node (ref "IC9") (pin "1") (pinfunction "L1_1") (pintype "output"))
    )
    (net (code "97") (name "Net-(IC9-L2)") (class "Default")
      (node (ref "DIS6") (pin "12") (pinfunction "12_12") (pintype "bidirectional"))
      (node (ref "IC9") (pin "18") (pinfunction "L2_18") (pintype "output"))
    )
    (net (code "98") (name "Net-(IC9-L3)") (class "Default")
      (node (ref "DIS6") (pin "13") (pinfunction "13_13") (pintype "bidirectional"))
      (node (ref "IC9") (pin "17") (pinfunction "L3_17") (pintype "output"))
    )
    (net (code "99") (name "Net-(IC9-L4)") (class "Default")
      (node (ref "DIS6") (pin "14") (pinfunction "14_14") (pintype "bidirectional"))
      (node (ref "IC9") (pin "16") (pinfunction "L4_16") (pintype "output"))
    )
    (net (code "100") (name "Net-(IC9-L5)") (class "Default")
      (node (ref "DIS6") (pin "15") (pinfunction "15_15") (pintype "bidirectional"))
      (node (ref "IC9") (pin "15") (pinfunction "L5_15") (pintype "output"))
    )
    (net (code "101") (name "Net-(IC9-L6)") (class "Default")
      (node (ref "DIS6") (pin "16") (pinfunction "16_16") (pintype "bidirectional"))
      (node (ref "IC9") (pin "14") (pinfunction "L6_14") (pintype "output"))
    )
    (net (code "102") (name "Net-(IC9-L7)") (class "Default")
      (node (ref "DIS6") (pin "17") (pinfunction "17_17") (pintype "bidirectional"))
      (node (ref "IC9") (pin "13") (pinfunction "L7_13") (pintype "output"))
    )
    (net (code "103") (name "Net-(IC9-L8)") (class "Default")
      (node (ref "DIS6") (pin "18") (pinfunction "18_18") (pintype "bidirectional"))
      (node (ref "IC9") (pin "12") (pinfunction "L8_12") (pintype "output"))
    )
    (net (code "104") (name "Net-(IC9-L9)") (class "Default")
      (node (ref "DIS6") (pin "19") (pinfunction "19_19") (pintype "bidirectional"))
      (node (ref "IC9") (pin "11") (pinfunction "L9_11") (pintype "output"))
    )
    (net (code "105") (name "Net-(IC9-L10)") (class "Default")
      (node (ref "DIS6") (pin "20") (pinfunction "20_20") (pintype "bidirectional"))
      (node (ref "IC9") (pin "10") (pinfunction "L10_10") (pintype "output"))
    )
    (net (code "106") (name "Net-(IC9-VR)") (class "Default")
      (node (ref "IC9") (pin "7") (pinfunction "VR_7") (pintype "output"))
      (node (ref "R65") (pin "2") (pinfunction "2_2") (pintype "passive"))
    )
    (net (code "107") (name "Net-(IC10-L1)") (class "Default")
      (node (ref "DIS7") (pin "11") (pinfunction "11_11") (pintype "bidirectional"))
      (node (ref "IC10") (pin "1") (pinfunction "L1_1") (pintype "output"))
    )
    (net (code "108") (name "Net-(IC10-L2)") (class "Default")
      (node (ref "DIS7") (pin "12") (pinfunction "12_12") (pintype "bidirectional"))
      (node (ref "IC10") (pin "18") (pinfunction "L2_18") (pintype "output"))
    )
    (net (code "109") (name "Net-(IC10-L3)") (class "Default")
      (node (ref "DIS7") (pin "13") (pinfunction "13_13") (pintype "bidirectional"))
      (node (ref "IC10") (pin "17") (pinfunction "L3_17") (pintype "output"))
    )
    (net (code "110") (name "Net-(IC10-L4)") (class "Default")
      (node (ref "DIS7") (pin "14") (pinfunction "14_14") (pintype "bidirectional"))
      (node (ref "IC10") (pin "16") (pinfunction "L4_16") (pintype "output"))
    )
    (net (code "111") (name "Net-(IC10-L5)") (class "Default")
      (node (ref "DIS7") (pin "15") (pinfunction "15_15") (pintype "bidirectional"))
      (node (ref "IC10") (pin "15") (pinfunction "L5_15") (pintype "output"))
    )
    (net (code "112") (name "Net-(IC10-L6)") (class "Default")
      (node (ref "DIS7") (pin "16") (pinfunction "16_16") (pintype "bidirectional"))
      (node (ref "IC10") (pin "14") (pinfunction "L6_14") (pintype "output"))
    )
    (net (code "113") (name "Net-(IC10-L7)") (class "Default")
      (node (ref "DIS7") (pin "17") (pinfunction "17_17") (pintype "bidirectional"))
      (node (ref "IC10") (pin "13") (pinfunction "L7_13") (pintype "output"))
    )
    (net (code "114") (name "Net-(IC10-L8)") (class "Default")
      (node (ref "DIS7") (pin "18") (pinfunction "18_18") (pintype "bidirectional"))
      (node (ref "IC10") (pin "12") (pinfunction "L8_12") (pintype "output"))
    )
    (net (code "115") (name "Net-(IC10-L9)") (class "Default")
      (node (ref "DIS7") (pin "19") (pinfunction "19_19") (pintype "bidirectional"))
      (node (ref "IC10") (pin "11") (pinfunction "L9_11") (pintype "output"))
    )
    (net (code "116") (name "Net-(IC10-L10)") (class "Default")
      (node (ref "DIS7") (pin "20") (pinfunction "20_20") (pintype "bidirectional"))
      (node (ref "IC10") (pin "10") (pinfunction "L10_10") (pintype "output"))
    )
    (net (code "117") (name "Net-(IC10-VR)") (class "Default")
      (node (ref "IC10") (pin "7") (pinfunction "VR_7") (pintype "output"))
      (node (ref "R66") (pin "2") (pinfunction "2_2") (pintype "passive"))
    )
    (net (code "118") (name "Net-(IC11-L1)") (class "Default")
      (node (ref "DIS8") (pin "11") (pinfunction "11_11") (pintype "bidirectional"))
      (node (ref "IC11") (pin "1") (pinfunction "L1_1") (pintype "output"))
    )
    (net (code "119") (name "Net-(IC11-L2)") (class "Default")
      (node (ref "DIS8") (pin "12") (pinfunction "12_12") (pintype "bidirectional"))
      (node (ref "IC11") (pin "18") (pinfunction "L2_18") (pintype "output"))
    )
    (net (code "120") (name "Net-(IC11-L3)") (class "Default")
      (node (ref "DIS8") (pin "13") (pinfunction "13_13") (pintype "bidirectional"))
      (node (ref "IC11") (pin "17") (pinfunction "L3_17") (pintype "output"))
    )
    (net (code "121") (name "Net-(IC11-L4)") (class "Default")
      (node (ref "DIS8") (pin "14") (pinfunction "14_14") (pintype "bidirectional"))
      (node (ref "IC11") (pin "16") (pinfunction "L4_16") (pintype "output"))
    )
    (net (code "122") (name "Net-(IC11-L5)") (class "Default")
      (node (ref "DIS8") (pin "15") (pinfunction "15_15") (pintype "bidirectional"))
      (node (ref "IC11") (pin "15") (pinfunction "L5_15") (pintype "output"))
    )
    (net (code "123") (name "Net-(IC11-L6)") (class "Default")
      (node (ref "DIS8") (pin "16") (pinfunction "16_16") (pintype "bidirectional"))
      (node (ref "IC11") (pin "14") (pinfunction "L6_14") (pintype "output"))
    )
    (net (code "124") (name "Net-(IC11-L7)") (class "Default")
      (node (ref "DIS8") (pin "17") (pinfunction "17_17") (pintype "bidirectional"))
      (node (ref "IC11") (pin "13") (pinfunction "L7_13") (pintype "output"))
    )
    (net (code "125") (name "Net-(IC11-L8)") (class "Default")
      (node (ref "DIS8") (pin "18") (pinfunction "18_18") (pintype "bidirectional"))
      (node (ref "IC11") (pin "12") (pinfunction "L8_12") (pintype "output"))
    )
    (net (code "126") (name "Net-(IC11-L9)") (class "Default")
      (node (ref "DIS8") (pin "19") (pinfunction "19_19") (pintype "bidirectional"))
      (node (ref "IC11") (pin "11") (pinfunction "L9_11") (pintype "output"))
    )
    (net (code "127") (name "Net-(IC11-L10)") (class "Default")
      (node (ref "DIS8") (pin "20") (pinfunction "20_20") (pintype "bidirectional"))
      (node (ref "IC11") (pin "10") (pinfunction "L10_10") (pintype "output"))
    )
    (net (code "128") (name "Net-(IC11-VR)") (class "Default")
      (node (ref "IC11") (pin "7") (pinfunction "VR_7") (pintype "output"))
      (node (ref "R67") (pin "2") (pinfunction "2_2") (pintype "passive"))
    )
    (net (code "129") (name "Net-(IC12-L1)") (class "Default")
      (node (ref "DIS9") (pin "11") (pinfunction "11_11") (pintype "bidirectional"))
      (node (ref "IC12") (pin "1") (pinfunction "L1_1") (pintype "output"))
    )
    (net (code "130") (name "Net-(IC12-L2)") (class "Default")
      (node (ref "DIS9") (pin "12") (pinfunction "12_12") (pintype "bidirectional"))
      (node (ref "IC12") (pin "18") (pinfunction "L2_18") (pintype "output"))
    )
    (net (code "131") (name "Net-(IC12-L3)") (class "Default")
      (node (ref "DIS9") (pin "13") (pinfunction "13_13") (pintype "bidirectional"))
      (node (ref "IC12") (pin "17") (pinfunction "L3_17") (pintype "output"))
    )
    (net (code "132") (name "Net-(IC12-L4)") (class "Default")
      (node (ref "DIS9") (pin "14") (pinfunction "14_14") (pintype "bidirectional"))
      (node (ref "IC12") (pin "16") (pinfunction "L4_16") (pintype "output"))
    )
    (net (code "133") (name "Net-(IC12-L5)") (class "Default")
      (node (ref "DIS9") (pin "15") (pinfunction "15_15") (pintype "bidirectional"))
      (node (ref "IC12") (pin "15") (pinfunction "L5_15") (pintype "output"))
    )
    (net (code "134") (name "Net-(IC12-L6)") (class "Default")
      (node (ref "DIS9") (pin "16") (pinfunction "16_16") (pintype "bidirectional"))
      (node (ref "IC12") (pin "14") (pinfunction "L6_14") (pintype "output"))
    )
    (net (code "135") (name "Net-(IC12-L7)") (class "Default")
      (node (ref "DIS9") (pin "17") (pinfunction "17_17") (pintype "bidirectional"))
      (node (ref "IC12") (pin "13") (pinfunction "L7_13") (pintype "output"))
    )
    (net (code "136") (name "Net-(IC12-L8)") (class "Default")
      (node (ref "DIS9") (pin "18") (pinfunction "18_18") (pintype "bidirectional"))
      (node (ref "IC12") (pin "12") (pinfunction "L8_12") (pintype "output"))
    )
    (net (code "137") (name "Net-(IC12-L9)") (class "Default")
      (node (ref "DIS9") (pin "19") (pinfunction "19_19") (pintype "bidirectional"))
      (node (ref "IC12") (pin "11") (pinfunction "L9_11") (pintype "output"))
    )
    (net (code "138") (name "Net-(IC12-L10)") (class "Default")
      (node (ref "DIS9") (pin "20") (pinfunction "20_20") (pintype "bidirectional"))
      (node (ref "IC12") (pin "10") (pinfunction "L10_10") (pintype "output"))
    )
    (net (code "139") (name "Net-(IC12-VR)") (class "Default")
      (node (ref "IC12") (pin "7") (pinfunction "VR_7") (pintype "output"))
      (node (ref "R68") (pin "2") (pinfunction "2_2") (pintype "passive"))
    )
    (net (code "140") (name "Net-(IC13-L1)") (class "Default")
      (node (ref "DIS10") (pin "11") (pinfunction "11_11") (pintype "bidirectional"))
      (node (ref "IC13") (pin "1") (pinfunction "L1_1") (pintype "output"))
    )
    (net (code "141") (name "Net-(IC13-L2)") (class "Default")
      (node (ref "DIS10") (pin "12") (pinfunction "12_12") (pintype "bidirectional"))
      (node (ref "IC13") (pin "18") (pinfunction "L2_18") (pintype "output"))
    )
    (net (code "142") (name "Net-(IC13-L3)") (class "Default")
      (node (ref "DIS10") (pin "13") (pinfunction "13_13") (pintype "bidirectional"))
      (node (ref "IC13") (pin "17") (pinfunction "L3_17") (pintype "output"))
    )
    (net (code "143") (name "Net-(IC13-L4)") (class "Default")
      (node (ref "DIS10") (pin "14") (pinfunction "14_14") (pintype "bidirectional"))
      (node (ref "IC13") (pin "16") (pinfunction "L4_16") (pintype "output"))
    )
    (net (code "144") (name "Net-(IC13-L5)") (class "Default")
      (node (ref "DIS10") (pin "15") (pinfunction "15_15") (pintype "bidirectional"))
      (node (ref "IC13") (pin "15") (pinfunction "L5_15") (pintype "output"))
    )
    (net (code "145") (name "Net-(IC13-L6)") (class "Default")
      (node (ref "DIS10") (pin "16") (pinfunction "16_16") (pintype "bidirectional"))
      (node (ref "IC13") (pin "14") (pinfunction "L6_14") (pintype "output"))
    )
    (net (code "146") (name "Net-(IC13-L7)") (class "Default")
      (node (ref "DIS10") (pin "17") (pinfunction "17_17") (pintype "bidirectional"))
      (node (ref "IC13") (pin "13") (pinfunction "L7_13") (pintype "output"))
    )
    (net (code "147") (name "Net-(IC13-L8)") (class "Default")
      (node (ref "DIS10") (pin "18") (pinfunction "18_18") (pintype "bidirectional"))
      (node (ref "IC13") (pin "12") (pinfunction "L8_12") (pintype "output"))
    )
    (net (code "148") (name "Net-(IC13-L9)") (class "Default")
      (node (ref "DIS10") (pin "19") (pinfunction "19_19") (pintype "bidirectional"))
      (node (ref "IC13") (pin "11") (pinfunction "L9_11") (pintype "output"))
    )
    (net (code "149") (name "Net-(IC13-L10)") (class "Default")
      (node (ref "DIS10") (pin "20") (pinfunction "20_20") (pintype "bidirectional"))
      (node (ref "IC13") (pin "10") (pinfunction "L10_10") (pintype "output"))
    )
    (net (code "150") (name "Net-(IC13-VR)") (class "Default")
      (node (ref "IC13") (pin "7") (pinfunction "VR_7") (pintype "output"))
      (node (ref "R69") (pin "2") (pinfunction "2_2") (pintype "passive"))
    )
    (net (code "151") (name "Net-(J1-L)") (class "Default")
      (node (ref "J1") (pin "3") (pinfunction "L_3") (pintype "bidirectional"))
      (node (ref "R3") (pin "1") (pinfunction "1_1") (pintype "passive"))
    )
    (net (code "152") (name "Net-(J1-R)") (class "Default")
      (node (ref "J1") (pin "2") (pinfunction "R_2") (pintype "bidirectional"))
      (node (ref "R2") (pin "1") (pinfunction "1_1") (pintype "passive"))
    )
    (net (code "153") (name "Net-(Q1-2)") (class "Default")
      (node (ref "C1") (pin "-") (pinfunction "-_-") (pintype "passive"))
      (node (ref "Q1") (pin "+") (pinfunction "2_+") (pintype "passive"))
      (node (ref "R1") (pin "1") (pinfunction "1_1") (pintype "passive"))
    )
    (net (code "154") (name "Net-(R4-E)") (class "Default")
      (node (ref "R4") (pin "3") (pinfunction "E_3") (pintype "passive"))
      (node (ref "R8") (pin "1") (pinfunction "1_1") (pintype "passive"))
    )
    (net (code "155") (name "Net-(R5-E)") (class "Default")
      (node (ref "R11") (pin "1") (pinfunction "1_1") (pintype "passive"))
      (node (ref "R5") (pin "3") (pinfunction "E_3") (pintype "passive"))
    )
    (net (code "156") (name "OUT1") (class "Default")
      (node (ref "C12") (pin "+") (pinfunction "+_+") (pintype "passive"))
      (node (ref "D1") (pin "C") (pinfunction "C_C") (pintype "passive"))
      (node (ref "IC4") (pin "5") (pinfunction "SIG_5") (pintype "input"))
      (node (ref "R22") (pin "2") (pinfunction "2_2") (pintype "passive"))
    )
    (net (code "157") (name "OUT2") (class "Default")
      (node (ref "C13") (pin "+") (pinfunction "+_+") (pintype "passive"))
      (node (ref "D2") (pin "C") (pinfunction "C_C") (pintype "passive"))
      (node (ref "IC5") (pin "5") (pinfunction "SIG_5") (pintype "input"))
      (node (ref "R23") (pin "2") (pinfunction "2_2") (pintype "passive"))
    )
    (net (code "158") (name "OUT3") (class "Default")
      (node (ref "C22") (pin "+") (pinfunction "+_+") (pintype "passive"))
      (node (ref "D3") (pin "C") (pinfunction "C_C") (pintype "passive"))
      (node (ref "IC6") (pin "5") (pinfunction "SIG_5") (pintype "input"))
      (node (ref "R36") (pin "2") (pinfunction "2_2") (pintype "passive"))
    )
    (net (code "159") (name "OUT4") (class "Default")
      (node (ref "C23") (pin "+") (pinfunction "+_+") (pintype "passive"))
      (node (ref "D4") (pin "C") (pinfunction "C_C") (pintype "passive"))
      (node (ref "IC7") (pin "5") (pinfunction "SIG_5") (pintype "input"))
      (node (ref "R37") (pin "2") (pinfunction "2_2") (pintype "passive"))
    )
    (net (code "160") (name "OUT5") (class "Default")
      (node (ref "C24") (pin "+") (pinfunction "+_+") (pintype "passive"))
      (node (ref "D5") (pin "C") (pinfunction "C_C") (pintype "passive"))
      (node (ref "IC8") (pin "5") (pinfunction "SIG_5") (pintype "input"))
      (node (ref "R38") (pin "2") (pinfunction "2_2") (pintype "passive"))
    )
    (net (code "161") (name "OUT6") (class "Default")
      (node (ref "C25") (pin "+") (pinfunction "+_+") (pintype "passive"))
      (node (ref "D6") (pin "C") (pinfunction "C_C") (pintype "passive"))
      (node (ref "IC9") (pin "5") (pinfunction "SIG_5") (pintype "input"))
      (node (ref "R39") (pin "2") (pinfunction "2_2") (pintype "passive"))
    )
    (net (code "162") (name "OUT7") (class "Default")
      (node (ref "C34") (pin "+") (pinfunction "+_+") (pintype "passive"))
      (node (ref "D8") (pin "C") (pinfunction "C_C") (pintype "passive"))
      (node (ref "IC10") (pin "5") (pinfunction "SIG_5") (pintype "input"))
      (node (ref "R52") (pin "2") (pinfunction "2_2") (pintype "passive"))
    )
    (net (code "163") (name "OUT8") (class "Default")
      (node (ref "C35") (pin "+") (pinfunction "+_+") (pintype "passive"))
      (node (ref "D9") (pin "C") (pinfunction "C_C") (pintype "passive"))
      (node (ref "IC11") (pin "5") (pinfunction "SIG_5") (pintype "input"))
      (node (ref "R53") (pin "2") (pinfunction "2_2") (pintype "passive"))
    )
    (net (code "164") (name "OUT9") (class "Default")
      (node (ref "C36") (pin "+") (pinfunction "+_+") (pintype "passive"))
      (node (ref "D10") (pin "C") (pinfunction "C_C") (pintype "passive"))
      (node (ref "IC12") (pin "5") (pinfunction "SIG_5") (pintype "input"))
      (node (ref "R54") (pin "2") (pinfunction "2_2") (pintype "passive"))
    )
    (net (code "165") (name "OUT10") (class "Default")
      (node (ref "C37") (pin "+") (pinfunction "+_+") (pintype "passive"))
      (node (ref "D11") (pin "C") (pinfunction "C_C") (pintype "passive"))
      (node (ref "IC13") (pin "5") (pinfunction "SIG_5") (pintype "input"))
      (node (ref "R55") (pin "2") (pinfunction "2_2") (pintype "passive"))
    )
    (net (code "166") (name "REF") (class "Default")
      (node (ref "D7") (pin "A") (pinfunction "A_A") (pintype "passive"))
      (node (ref "IC1") (pin "10") (pinfunction "+IN_10") (pintype "input"))
      (node (ref "IC1") (pin "12") (pinfunction "+IN_12") (pintype "input"))
      (node (ref "IC2") (pin "10") (pinfunction "+IN_10") (pintype "input"))
      (node (ref "IC2") (pin "12") (pinfunction "+IN_12") (pintype "input"))
      (node (ref "IC2") (pin "3") (pinfunction "+IN_3") (pintype "input"))
      (node (ref "IC2") (pin "5") (pinfunction "+IN_5") (pintype "input"))
      (node (ref "IC3") (pin "10") (pinfunction "+IN_10") (pintype "input"))
      (node (ref "IC3") (pin "12") (pinfunction "+IN_12") (pintype "input"))
      (node (ref "IC3") (pin "3") (pinfunction "+IN_3") (pintype "input"))
      (node (ref "IC3") (pin "5") (pinfunction "+IN_5") (pintype "input"))
      (node (ref "R19") (pin "1") (pinfunction "1_1") (pintype "passive"))
    )
    (net (code "167") (name "RHI") (class "Default")
      (node (ref "IC10") (pin "6") (pinfunction "RHI_6") (pintype "input"))
      (node (ref "IC11") (pin "6") (pinfunction "RHI_6") (pintype "input"))
      (node (ref "IC12") (pin "6") (pinfunction "RHI_6") (pintype "input"))
      (node (ref "IC13") (pin "6") (pinfunction "RHI_6") (pintype "input"))
      (node (ref "IC4") (pin "6") (pinfunction "RHI_6") (pintype "input"))
      (node (ref "IC5") (pin "6") (pinfunction "RHI_6") (pintype "input"))
      (node (ref "IC6") (pin "6") (pinfunction "RHI_6") (pintype "input"))
      (node (ref "IC7") (pin "6") (pinfunction "RHI_6") (pintype "input"))
      (node (ref "IC8") (pin "6") (pinfunction "RHI_6") (pintype "input"))
      (node (ref "IC9") (pin "6") (pinfunction "RHI_6") (pintype "input"))
      (node (ref "R58") (pin "1") (pinfunction "1_1") (pintype "passive"))
      (node (ref "R59") (pin "2") (pinfunction "2_2") (pintype "passive"))
      (node (ref "TP4") (pin "TP") (pinfunction "TP_TP") (pintype "input"))
    )
    (net (code "168") (name "RLO") (class "Default")
      (node (ref "IC10") (pin "4") (pinfunction "RLO_4") (pintype "input"))
      (node (ref "IC11") (pin "4") (pinfunction "RLO_4") (pintype "input"))
      (node (ref "IC12") (pin "4") (pinfunction "RLO_4") (pintype "input"))
      (node (ref "IC13") (pin "4") (pinfunction "RLO_4") (pintype "input"))
      (node (ref "IC4") (pin "4") (pinfunction "RLO_4") (pintype "input"))
      (node (ref "IC5") (pin "4") (pinfunction "RLO_4") (pintype "input"))
      (node (ref "IC6") (pin "4") (pinfunction "RLO_4") (pintype "input"))
      (node (ref "IC7") (pin "4") (pinfunction "RLO_4") (pintype "input"))
      (node (ref "IC8") (pin "4") (pinfunction "RLO_4") (pintype "input"))
      (node (ref "IC9") (pin "4") (pinfunction "RLO_4") (pintype "input"))
      (node (ref "R56") (pin "1") (pinfunction "1_1") (pintype "passive"))
      (node (ref "R57") (pin "2") (pinfunction "2_2") (pintype "passive"))
      (node (ref "TP5") (pin "TP") (pinfunction "TP_TP") (pintype "input"))
    )
    (net (code "169") (name "V+") (class "Default")
      (node (ref "C38") (pin "1") (pinfunction "1_1") (pintype "passive"))
      (node (ref "C39") (pin "1") (pinfunction "1_1") (pintype "passive"))
      (node (ref "C40") (pin "1") (pinfunction "1_1") (pintype "passive"))
      (node (ref "C41") (pin "1") (pinfunction "1_1") (pintype "passive"))
      (node (ref "C42") (pin "1") (pinfunction "1_1") (pintype "passive"))
      (node (ref "C43") (pin "1") (pinfunction "1_1") (pintype "passive"))
      (node (ref "C44") (pin "1") (pinfunction "1_1") (pintype "passive"))
      (node (ref "C45") (pin "1") (pinfunction "1_1") (pintype "passive"))
      (node (ref "C46") (pin "1") (pinfunction "1_1") (pintype "passive"))
      (node (ref "C47") (pin "1") (pinfunction "1_1") (pintype "passive"))
      (node (ref "C5") (pin "1") (pinfunction "1_1") (pintype "passive"))
      (node (ref "C6") (pin "1") (pinfunction "1_1") (pintype "passive"))
      (node (ref "C7") (pin "1") (pinfunction "1_1") (pintype "passive"))
      (node (ref "DIS1") (pin "1") (pinfunction "1_1") (pintype "bidirectional"))
      (node (ref "DIS1") (pin "10") (pinfunction "10_10") (pintype "bidirectional"))
      (node (ref "DIS1") (pin "2") (pinfunction "2_2") (pintype "bidirectional"))
      (node (ref "DIS1") (pin "3") (pinfunction "3_3") (pintype "bidirectional"))
      (node (ref "DIS1") (pin "4") (pinfunction "4_4") (pintype "bidirectional"))
      (node (ref "DIS1") (pin "5") (pinfunction "5_5") (pintype "bidirectional"))
      (node (ref "DIS1") (pin "6") (pinfunction "6_6") (pintype "bidirectional"))
      (node (ref "DIS1") (pin "7") (pinfunction "7_7") (pintype "bidirectional"))
      (node (ref "DIS1") (pin "8") (pinfunction "8_8") (pintype "bidirectional"))
      (node (ref "DIS1") (pin "9") (pinfunction "9_9") (pintype "bidirectional"))
      (node (ref "DIS10") (pin "1") (pinfunction "1_1") (pintype "bidirectional"))
      (node (ref "DIS10") (pin "10") (pinfunction "10_10") (pintype "bidirectional"))
      (node (ref "DIS10") (pin "2") (pinfunction "2_2") (pintype "bidirectional"))
      (node (ref "DIS10") (pin "3") (pinfunction "3_3") (pintype "bidirectional"))
      (node (ref "DIS10") (pin "4") (pinfunction "4_4") (pintype "bidirectional"))
      (node (ref "DIS10") (pin "5") (pinfunction "5_5") (pintype "bidirectional"))
      (node (ref "DIS10") (pin "6") (pinfunction "6_6") (pintype "bidirectional"))
      (node (ref "DIS10") (pin "7") (pinfunction "7_7") (pintype "bidirectional"))
      (node (ref "DIS10") (pin "8") (pinfunction "8_8") (pintype "bidirectional"))
      (node (ref "DIS10") (pin "9") (pinfunction "9_9") (pintype "bidirectional"))
      (node (ref "DIS2") (pin "1") (pinfunction "1_1") (pintype "bidirectional"))
      (node (ref "DIS2") (pin "10") (pinfunction "10_10") (pintype "bidirectional"))
      (node (ref "DIS2") (pin "2") (pinfunction "2_2") (pintype "bidirectional"))
      (node (ref "DIS2") (pin "3") (pinfunction "3_3") (pintype "bidirectional"))
      (node (ref "DIS2") (pin "4") (pinfunction "4_4") (pintype "bidirectional"))
      (node (ref "DIS2") (pin "5") (pinfunction "5_5") (pintype "bidirectional"))
      (node (ref "DIS2") (pin "6") (pinfunction "6_6") (pintype "bidirectional"))
      (node (ref "DIS2") (pin "7") (pinfunction "7_7") (pintype "bidirectional"))
      (node (ref "DIS2") (pin "8") (pinfunction "8_8") (pintype "bidirectional"))
      (node (ref "DIS2") (pin "9") (pinfunction "9_9") (pintype "bidirectional"))
      (node (ref "DIS3") (pin "1") (pinfunction "1_1") (pintype "bidirectional"))
      (node (ref "DIS3") (pin "10") (pinfunction "10_10") (pintype "bidirectional"))
      (node (ref "DIS3") (pin "2") (pinfunction "2_2") (pintype "bidirectional"))
      (node (ref "DIS3") (pin "3") (pinfunction "3_3") (pintype "bidirectional"))
      (node (ref "DIS3") (pin "4") (pinfunction "4_4") (pintype "bidirectional"))
      (node (ref "DIS3") (pin "5") (pinfunction "5_5") (pintype "bidirectional"))
      (node (ref "DIS3") (pin "6") (pinfunction "6_6") (pintype "bidirectional"))
      (node (ref "DIS3") (pin "7") (pinfunction "7_7") (pintype "bidirectional"))
      (node (ref "DIS3") (pin "8") (pinfunction "8_8") (pintype "bidirectional"))
      (node (ref "DIS3") (pin "9") (pinfunction "9_9") (pintype "bidirectional"))
      (node (ref "DIS4") (pin "1") (pinfunction "1_1") (pintype "bidirectional"))
      (node (ref "DIS4") (pin "10") (pinfunction "10_10") (pintype "bidirectional"))
      (node (ref "DIS4") (pin "2") (pinfunction "2_2") (pintype "bidirectional"))
      (node (ref "DIS4") (pin "3") (pinfunction "3_3") (pintype "bidirectional"))
      (node (ref "DIS4") (pin "4") (pinfunction "4_4") (pintype "bidirectional"))
      (node (ref "DIS4") (pin "5") (pinfunction "5_5") (pintype "bidirectional"))
      (node (ref "DIS4") (pin "6") (pinfunction "6_6") (pintype "bidirectional"))
      (node (ref "DIS4") (pin "7") (pinfunction "7_7") (pintype "bidirectional"))
      (node (ref "DIS4") (pin "8") (pinfunction "8_8") (pintype "bidirectional"))
      (node (ref "DIS4") (pin "9") (pinfunction "9_9") (pintype "bidirectional"))
      (node (ref "DIS5") (pin "1") (pinfunction "1_1") (pintype "bidirectional"))
      (node (ref "DIS5") (pin "10") (pinfunction "10_10") (pintype "bidirectional"))
      (node (ref "DIS5") (pin "2") (pinfunction "2_2") (pintype "bidirectional"))
      (node (ref "DIS5") (pin "3") (pinfunction "3_3") (pintype "bidirectional"))
      (node (ref "DIS5") (pin "4") (pinfunction "4_4") (pintype "bidirectional"))
      (node (ref "DIS5") (pin "5") (pinfunction "5_5") (pintype "bidirectional"))
      (node (ref "DIS5") (pin "6") (pinfunction "6_6") (pintype "bidirectional"))
      (node (ref "DIS5") (pin "7") (pinfunction "7_7") (pintype "bidirectional"))
      (node (ref "DIS5") (pin "8") (pinfunction "8_8") (pintype "bidirectional"))
      (node (ref "DIS5") (pin "9") (pinfunction "9_9") (pintype "bidirectional"))
      (node (ref "DIS6") (pin "1") (pinfunction "1_1") (pintype "bidirectional"))
      (node (ref "DIS6") (pin "10") (pinfunction "10_10") (pintype "bidirectional"))
      (node (ref "DIS6") (pin "2") (pinfunction "2_2") (pintype "bidirectional"))
      (node (ref "DIS6") (pin "3") (pinfunction "3_3") (pintype "bidirectional"))
      (node (ref "DIS6") (pin "4") (pinfunction "4_4") (pintype "bidirectional"))
      (node (ref "DIS6") (pin "5") (pinfunction "5_5") (pintype "bidirectional"))
      (node (ref "DIS6") (pin "6") (pinfunction "6_6") (pintype "bidirectional"))
      (node (ref "DIS6") (pin "7") (pinfunction "7_7") (pintype "bidirectional"))
      (node (ref "DIS6") (pin "8") (pinfunction "8_8") (pintype "bidirectional"))
      (node (ref "DIS6") (pin "9") (pinfunction "9_9") (pintype "bidirectional"))
      (node (ref "DIS7") (pin "1") (pinfunction "1_1") (pintype "bidirectional"))
      (node (ref "DIS7") (pin "10") (pinfunction "10_10") (pintype "bidirectional"))
      (node (ref "DIS7") (pin "2") (pinfunction "2_2") (pintype "bidirectional"))
      (node (ref "DIS7") (pin "3") (pinfunction "3_3") (pintype "bidirectional"))
      (node (ref "DIS7") (pin "4") (pinfunction "4_4") (pintype "bidirectional"))
      (node (ref "DIS7") (pin "5") (pinfunction "5_5") (pintype "bidirectional"))
      (node (ref "DIS7") (pin "6") (pinfunction "6_6") (pintype "bidirectional"))
      (node (ref "DIS7") (pin "7") (pinfunction "7_7") (pintype "bidirectional"))
      (node (ref "DIS7") (pin "8") (pinfunction "8_8") (pintype "bidirectional"))
      (node (ref "DIS7") (pin "9") (pinfunction "9_9") (pintype "bidirectional"))
      (node (ref "DIS8") (pin "1") (pinfunction "1_1") (pintype "bidirectional"))
      (node (ref "DIS8") (pin "10") (pinfunction "10_10") (pintype "bidirectional"))
      (node (ref "DIS8") (pin "2") (pinfunction "2_2") (pintype "bidirectional"))
      (node (ref "DIS8") (pin "3") (pinfunction "3_3") (pintype "bidirectional"))
      (node (ref "DIS8") (pin "4") (pinfunction "4_4") (pintype "bidirectional"))
      (node (ref "DIS8") (pin "5") (pinfunction "5_5") (pintype "bidirectional"))
      (node (ref "DIS8") (pin "6") (pinfunction "6_6") (pintype "bidirectional"))
      (node (ref "DIS8") (pin "7") (pinfunction "7_7") (pintype "bidirectional"))
      (node (ref "DIS8") (pin "8") (pinfunction "8_8") (pintype "bidirectional"))
      (node (ref "DIS8") (pin "9") (pinfunction "9_9") (pintype "bidirectional"))
      (node (ref "DIS9") (pin "1") (pinfunction "1_1") (pintype "bidirectional"))
      (node (ref "DIS9") (pin "10") (pinfunction "10_10") (pintype "bidirectional"))
      (node (ref "DIS9") (pin "2") (pinfunction "2_2") (pintype "bidirectional"))
      (node (ref "DIS9") (pin "3") (pinfunction "3_3") (pintype "bidirectional"))
      (node (ref "DIS9") (pin "4") (pinfunction "4_4") (pintype "bidirectional"))
      (node (ref "DIS9") (pin "5") (pinfunction "5_5") (pintype "bidirectional"))
      (node (ref "DIS9") (pin "6") (pinfunction "6_6") (pintype "bidirectional"))
      (node (ref "DIS9") (pin "7") (pinfunction "7_7") (pintype "bidirectional"))
      (node (ref "DIS9") (pin "8") (pinfunction "8_8") (pintype "bidirectional"))
      (node (ref "DIS9") (pin "9") (pinfunction "9_9") (pintype "bidirectional"))
      (node (ref "IC1") (pin "4") (pinfunction "V+_4") (pintype "power_in"))
      (node (ref "IC10") (pin "3") (pinfunction "V+_3") (pintype "power_in"))
      (node (ref "IC10") (pin "9") (pinfunction "MDE_9") (pintype "input"))
      (node (ref "IC11") (pin "3") (pinfunction "V+_3") (pintype "power_in"))
      (node (ref "IC11") (pin "9") (pinfunction "MDE_9") (pintype "input"))
      (node (ref "IC12") (pin "3") (pinfunction "V+_3") (pintype "power_in"))
      (node (ref "IC12") (pin "9") (pinfunction "MDE_9") (pintype "input"))
      (node (ref "IC13") (pin "3") (pinfunction "V+_3") (pintype "power_in"))
      (node (ref "IC13") (pin "9") (pinfunction "MDE_9") (pintype "input"))
      (node (ref "IC2") (pin "4") (pinfunction "V+_4") (pintype "power_in"))
      (node (ref "IC3") (pin "4") (pinfunction "V+_4") (pintype "power_in"))
      (node (ref "IC4") (pin "3") (pinfunction "V+_3") (pintype "power_in"))
      (node (ref "IC4") (pin "9") (pinfunction "MDE_9") (pintype "input"))
      (node (ref "IC5") (pin "3") (pinfunction "V+_3") (pintype "power_in"))
      (node (ref "IC5") (pin "9") (pinfunction "MDE_9") (pintype "input"))
      (node (ref "IC6") (pin "3") (pinfunction "V+_3") (pintype "power_in"))
      (node (ref "IC6") (pin "9") (pinfunction "MDE_9") (pintype "input"))
      (node (ref "IC7") (pin "3") (pinfunction "V+_3") (pintype "power_in"))
      (node (ref "IC7") (pin "9") (pinfunction "MDE_9") (pintype "input"))
      (node (ref "IC8") (pin "3") (pinfunction "V+_3") (pintype "power_in"))
      (node (ref "IC8") (pin "9") (pinfunction "MDE_9") (pintype "input"))
      (node (ref "IC9") (pin "3") (pinfunction "V+_3") (pintype "power_in"))
      (node (ref "IC9") (pin "9") (pinfunction "MDE_9") (pintype "input"))
      (node (ref "J2") (pin "1") (pinfunction "1_1") (pintype "passive"))
      (node (ref "R1") (pin "2") (pinfunction "2_2") (pintype "passive"))
      (node (ref "R19") (pin "2") (pinfunction "2_2") (pintype "passive"))
      (node (ref "R56") (pin "2") (pinfunction "2_2") (pintype "passive"))
      (node (ref "R58") (pin "2") (pinfunction "2_2") (pintype "passive"))
      (node (ref "R6") (pin "2") (pinfunction "2_2") (pintype "passive"))
      (node (ref "R9") (pin "2") (pinfunction "2_2") (pintype "passive"))
      (node (ref "TP1") (pin "TP") (pinfunction "TP_TP") (pintype "input"))
    )
    (net (code "170") (name "VER") (class "Default")
      (node (ref "C4") (pin "-") (pinfunction "-_-") (pintype "passive"))
      (node (ref "R14") (pin "2") (pinfunction "2_2") (pintype "passive"))
      (node (ref "R15") (pin "1") (pinfunction "1_1") (pintype "passive"))
      (node (ref "R16") (pin "1") (pinfunction "1_1") (pintype "passive"))
      (node (ref "R24") (pin "1") (pinfunction "1_1") (pintype "passive"))
      (node (ref "R25") (pin "1") (pinfunction "1_1") (pintype "passive"))
      (node (ref "R26") (pin "1") (pinfunction "1_1") (pintype "passive"))
      (node (ref "R27") (pin "1") (pinfunction "1_1") (pintype "passive"))
      (node (ref "R40") (pin "1") (pinfunction "1_1") (pintype "passive"))
      (node (ref "R41") (pin "1") (pinfunction "1_1") (pintype "passive"))
      (node (ref "R42") (pin "1") (pinfunction "1_1") (pintype "passive"))
      (node (ref "R43") (pin "1") (pinfunction "1_1") (pintype "passive"))
      (node (ref "TP3") (pin "TP") (pinfunction "TP_TP") (pintype "input"))
    )
    (net (code "171") (name "unconnected-(R4-A-Pad1)") (class "Default")
      (node (ref "R4") (pin "1") (pinfunction "A_1") (pintype "passive"))
    )
    (net (code "172") (name "unconnected-(R5-A-Pad1)") (class "Default")
      (node (ref "R5") (pin "1") (pinfunction "A_1") (pintype "passive"))
    )
  )
)
